# board2-c.net
KiCad netlist of a schematic drawn in EAGLE
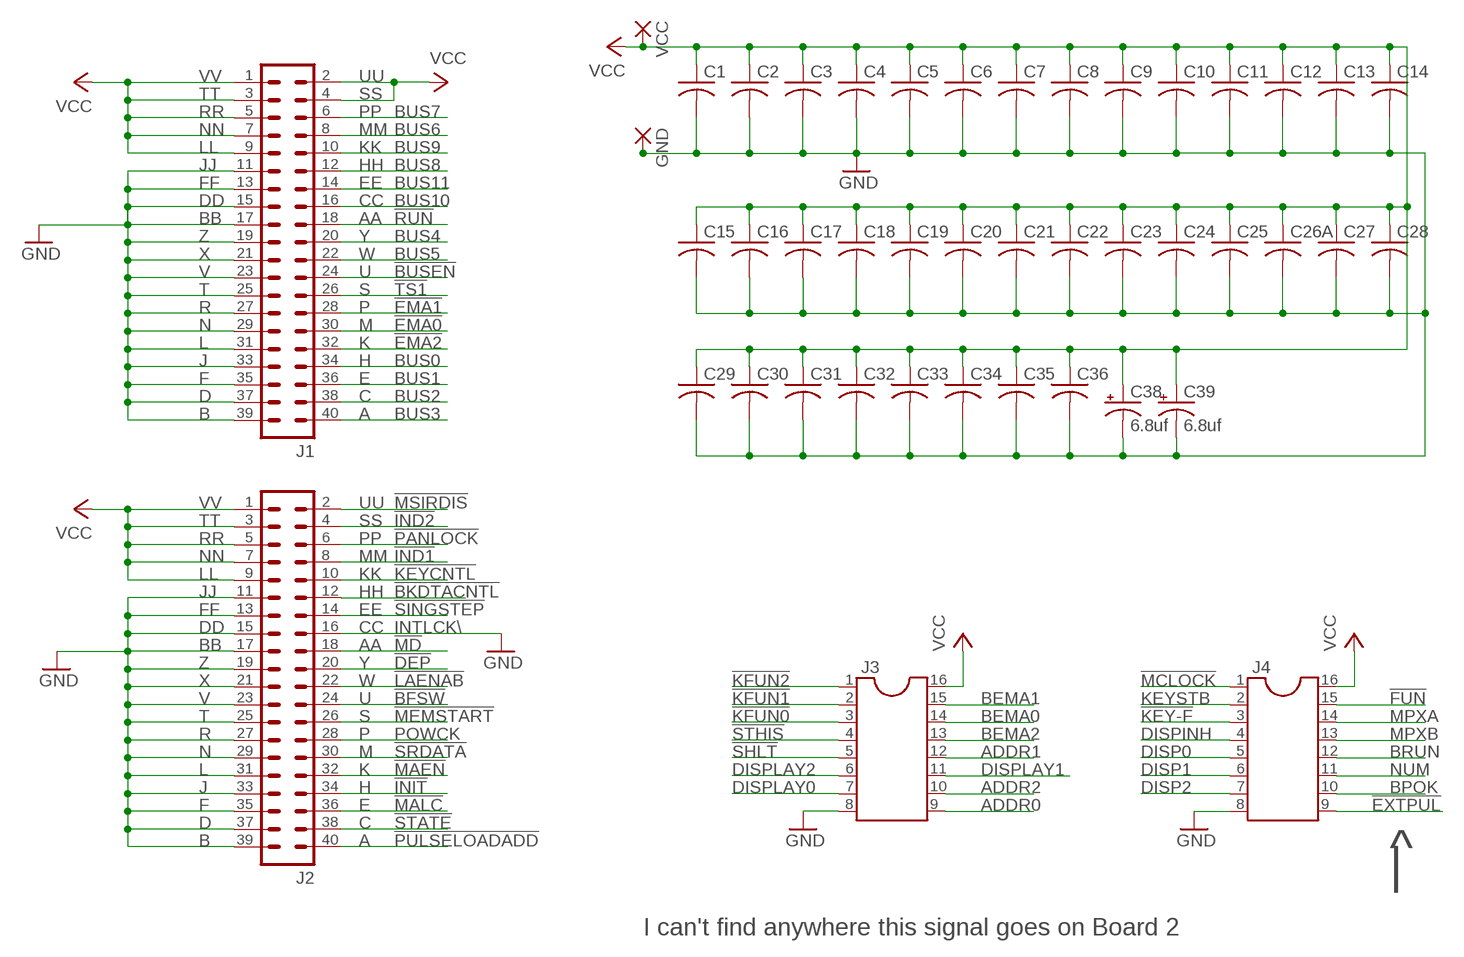
[diagram p0: schematic, sheet 1]
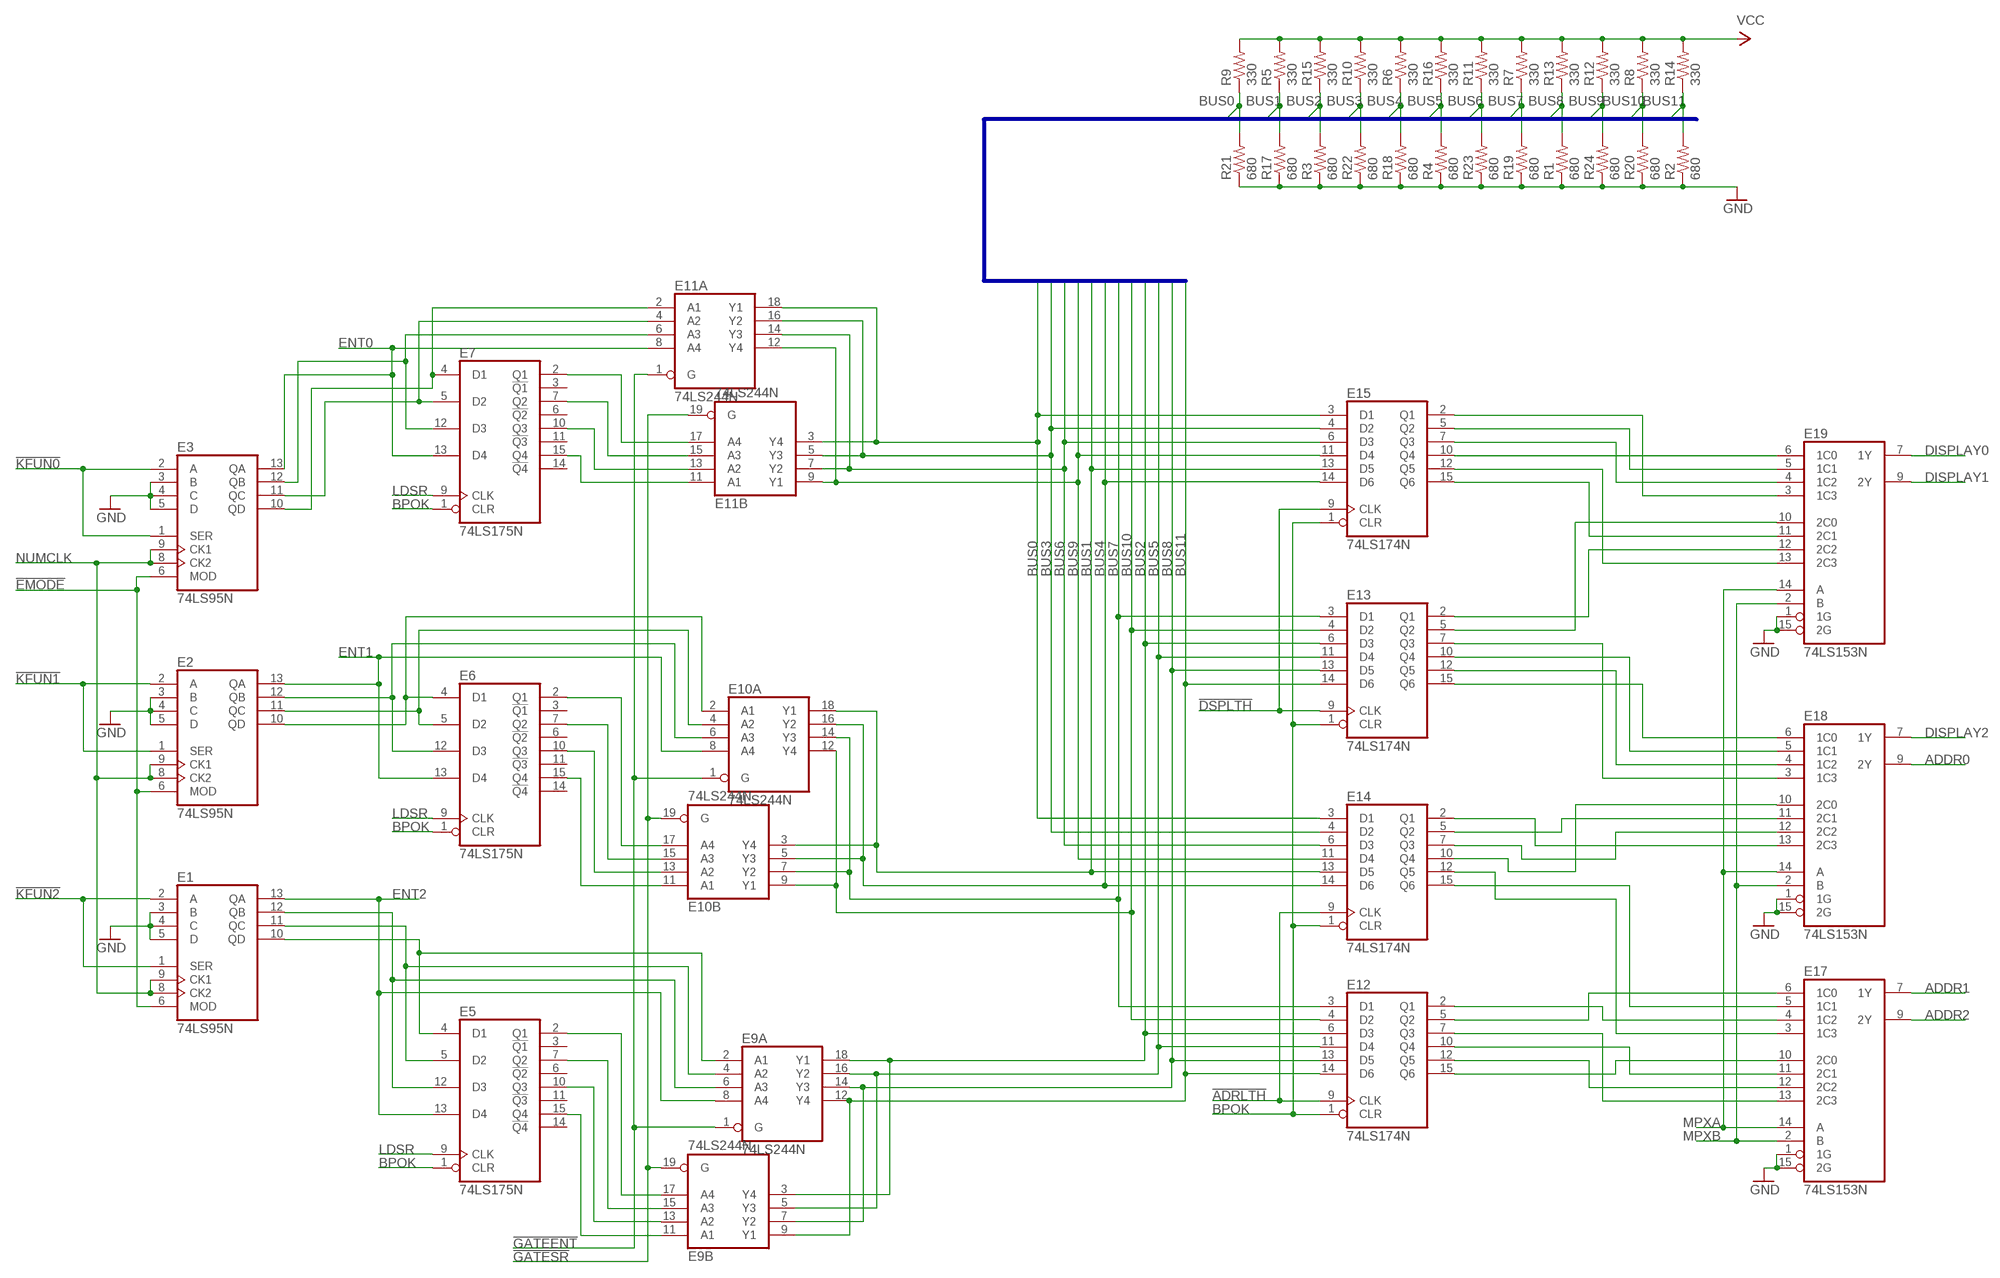
[diagram p1: schematic, sheet 2]
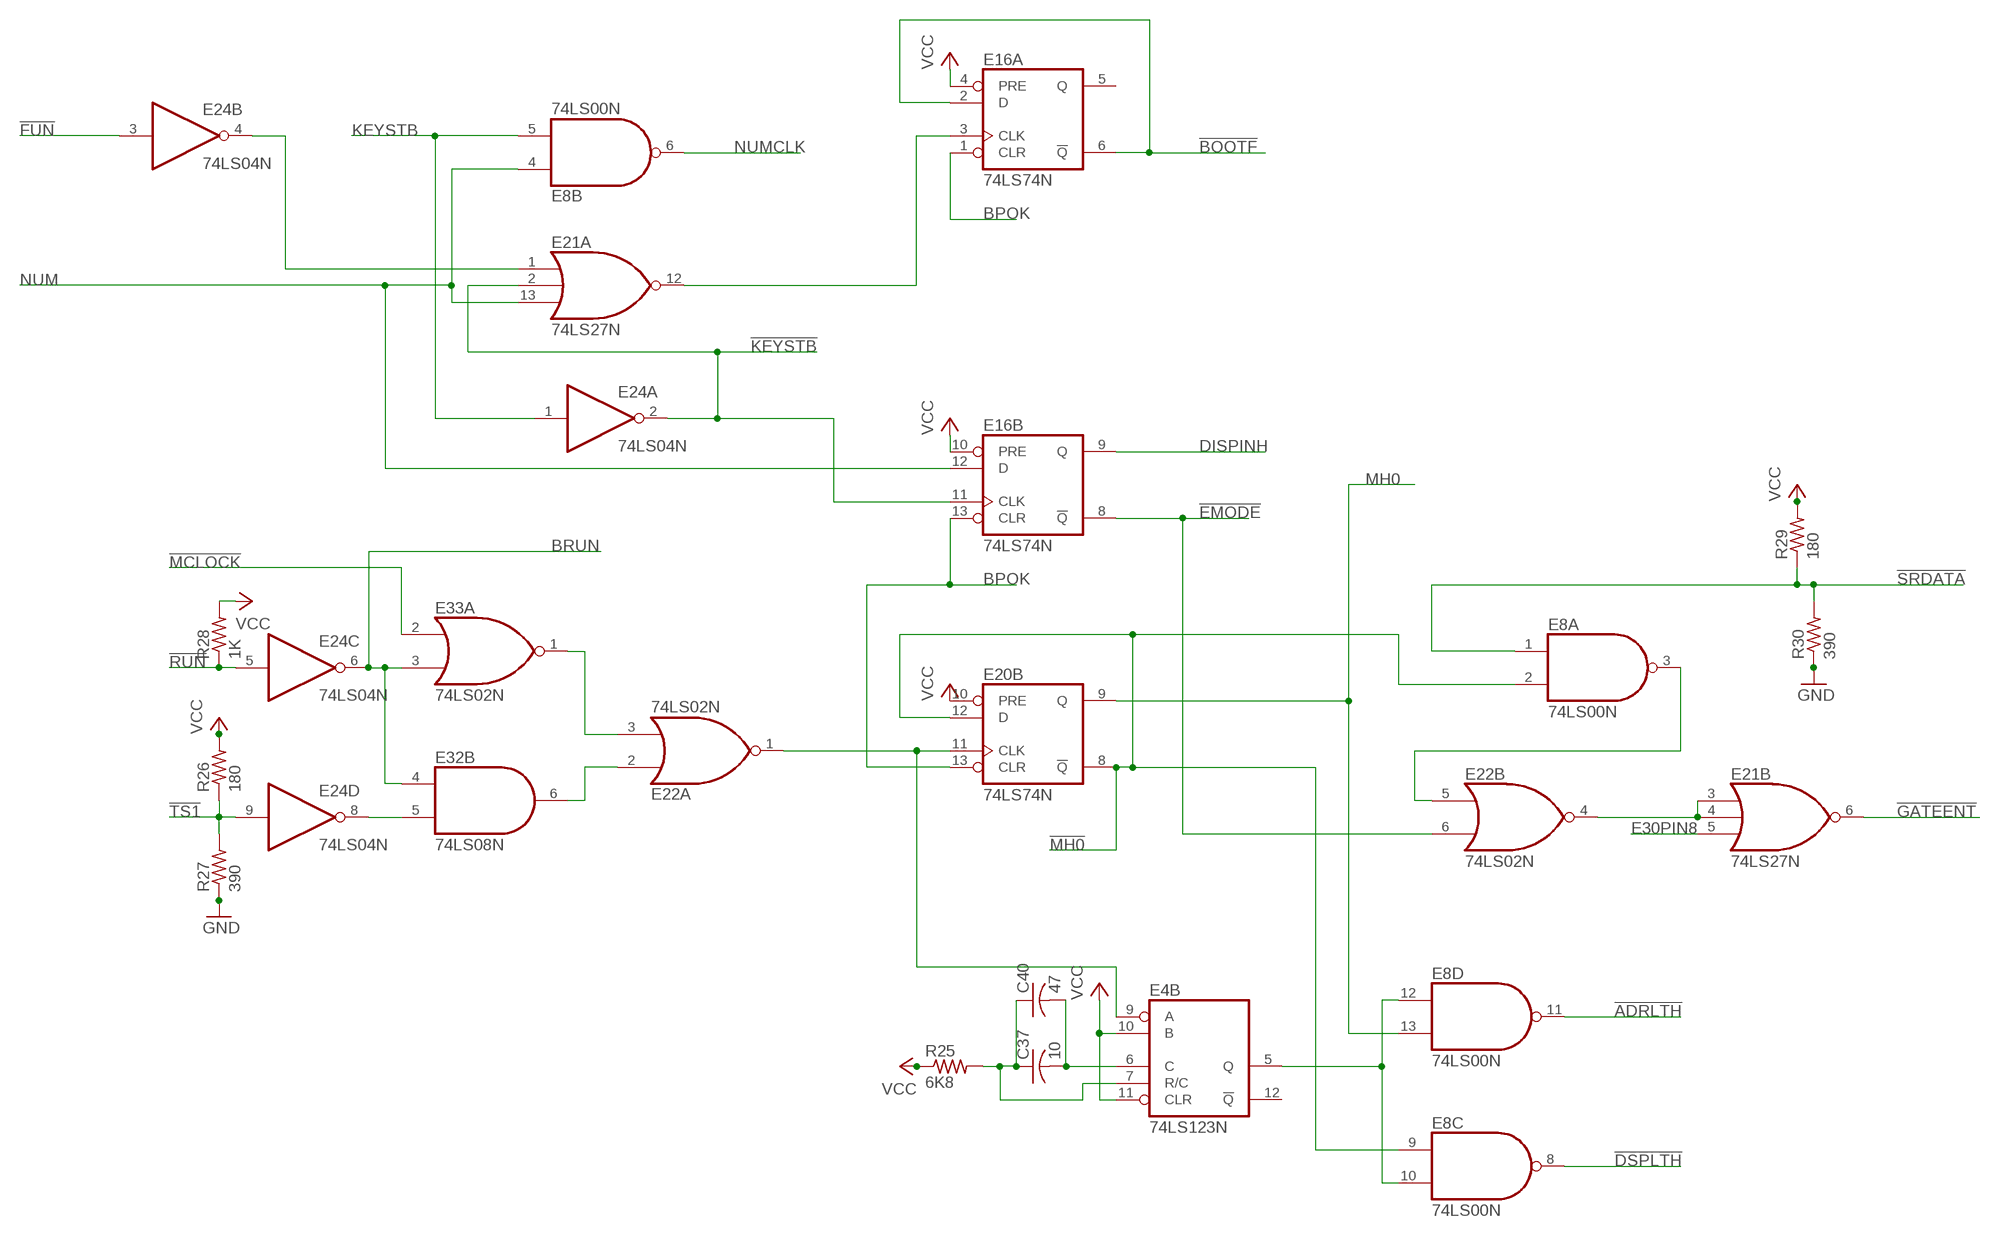
[diagram p2: schematic, sheet 3]
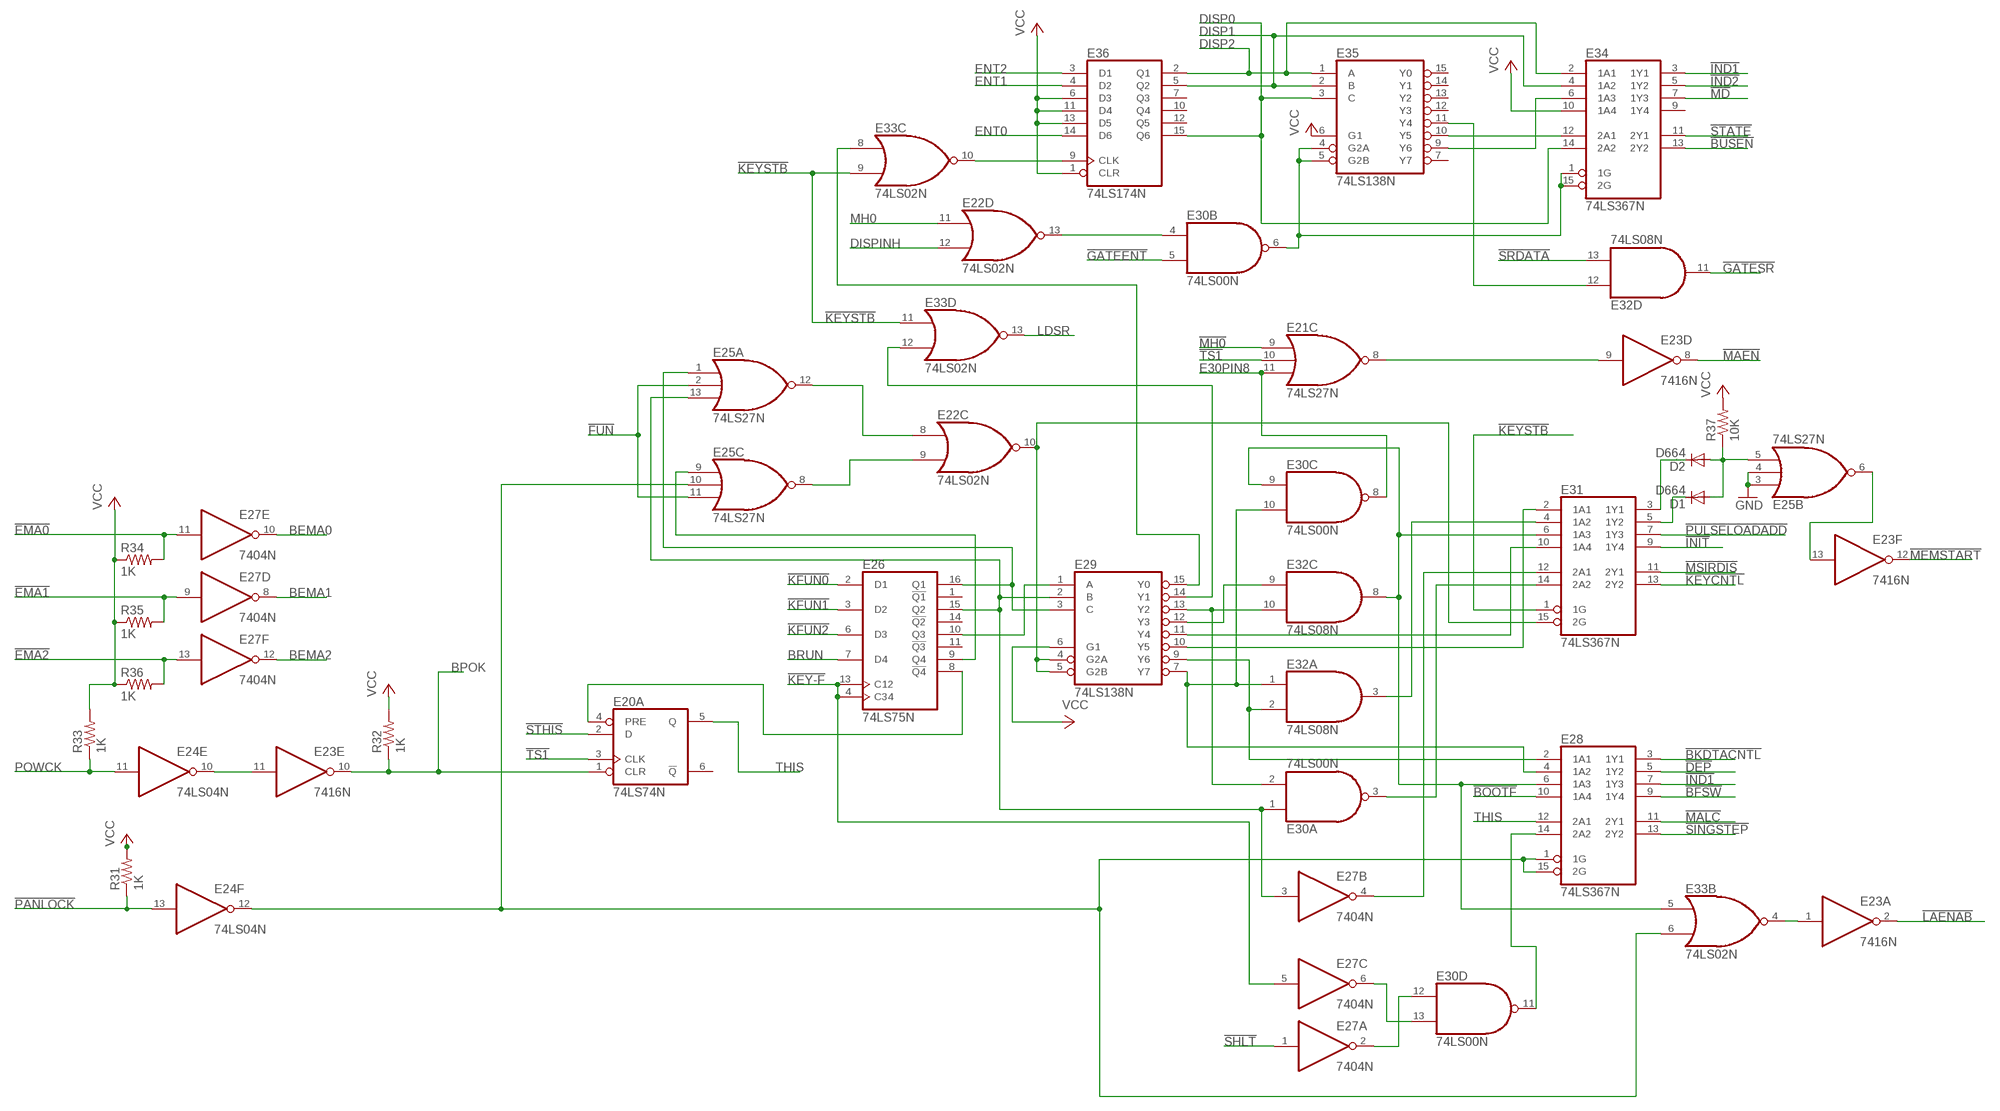
[diagram p3: schematic, sheet 4]

(export (version "E")
  (design (tool "Eeschema 10.0.6"))
  (components
    (comp (ref "C1")
      (value "C-US050-025X075")
      (footprint "eagle-import:C050-025X075")
      (libsource (lib "eagle-import") (part "C-US050-025X075"))
    )
    (comp (ref "C2")
      (value "C-US050-025X075")
      (footprint "eagle-import:C050-025X075")
      (libsource (lib "eagle-import") (part "C-US050-025X075"))
    )
    (comp (ref "C3")
      (value "C-US050-025X075")
      (footprint "eagle-import:C050-025X075")
      (libsource (lib "eagle-import") (part "C-US050-025X075"))
    )
    (comp (ref "C4")
      (value "C-US050-025X075")
      (footprint "eagle-import:C050-025X075")
      (libsource (lib "eagle-import") (part "C-US050-025X075"))
    )
    (comp (ref "C5")
      (value "C-US050-025X075")
      (footprint "eagle-import:C050-025X075")
      (libsource (lib "eagle-import") (part "C-US050-025X075"))
    )
    (comp (ref "C6")
      (value "C-US050-025X075")
      (footprint "eagle-import:C050-025X075")
      (libsource (lib "eagle-import") (part "C-US050-025X075"))
    )
    (comp (ref "C7")
      (value "C-US050-025X075")
      (footprint "eagle-import:C050-025X075")
      (libsource (lib "eagle-import") (part "C-US050-025X075"))
    )
    (comp (ref "C8")
      (value "C-US050-025X075")
      (footprint "eagle-import:C050-025X075")
      (libsource (lib "eagle-import") (part "C-US050-025X075"))
    )
    (comp (ref "C9")
      (value "C-US050-025X075")
      (footprint "eagle-import:C050-025X075")
      (libsource (lib "eagle-import") (part "C-US050-025X075"))
    )
    (comp (ref "C10")
      (value "C-US050-025X075")
      (footprint "eagle-import:C050-025X075")
      (libsource (lib "eagle-import") (part "C-US050-025X075"))
    )
    (comp (ref "C11")
      (value "C-US050-025X075")
      (footprint "eagle-import:C050-025X075")
      (libsource (lib "eagle-import") (part "C-US050-025X075"))
    )
    (comp (ref "C12")
      (value "C-US050-025X075")
      (footprint "eagle-import:C050-025X075")
      (libsource (lib "eagle-import") (part "C-US050-025X075"))
    )
    (comp (ref "C13")
      (value "C-US050-025X075")
      (footprint "eagle-import:C050-025X075")
      (libsource (lib "eagle-import") (part "C-US050-025X075"))
    )
    (comp (ref "C14")
      (value "C-US050-025X075")
      (footprint "eagle-import:C050-025X075")
      (libsource (lib "eagle-import") (part "C-US050-025X075"))
    )
    (comp (ref "C15")
      (value "C-US050-025X075")
      (footprint "eagle-import:C050-025X075")
      (libsource (lib "eagle-import") (part "C-US050-025X075"))
    )
    (comp (ref "C16")
      (value "C-US050-025X075")
      (footprint "eagle-import:C050-025X075")
      (libsource (lib "eagle-import") (part "C-US050-025X075"))
    )
    (comp (ref "C17")
      (value "C-US050-025X075")
      (footprint "eagle-import:C050-025X075")
      (libsource (lib "eagle-import") (part "C-US050-025X075"))
    )
    (comp (ref "C18")
      (value "C-US050-025X075")
      (footprint "eagle-import:C050-025X075")
      (libsource (lib "eagle-import") (part "C-US050-025X075"))
    )
    (comp (ref "C19")
      (value "C-US050-025X075")
      (footprint "eagle-import:C050-025X075")
      (libsource (lib "eagle-import") (part "C-US050-025X075"))
    )
    (comp (ref "C20")
      (value "C-US050-025X075")
      (footprint "eagle-import:C050-025X075")
      (libsource (lib "eagle-import") (part "C-US050-025X075"))
    )
    (comp (ref "C21")
      (value "C-US050-025X075")
      (footprint "eagle-import:C050-025X075")
      (libsource (lib "eagle-import") (part "C-US050-025X075"))
    )
    (comp (ref "C22")
      (value "C-US050-025X075")
      (footprint "eagle-import:C050-025X075")
      (libsource (lib "eagle-import") (part "C-US050-025X075"))
    )
    (comp (ref "C23")
      (value "C-US050-025X075")
      (footprint "eagle-import:C050-025X075")
      (libsource (lib "eagle-import") (part "C-US050-025X075"))
    )
    (comp (ref "C24")
      (value "C-US050-025X075")
      (footprint "eagle-import:C050-025X075")
      (libsource (lib "eagle-import") (part "C-US050-025X075"))
    )
    (comp (ref "C25")
      (value "C-US050-025X075")
      (footprint "eagle-import:C050-025X075")
      (libsource (lib "eagle-import") (part "C-US050-025X075"))
    )
    (comp (ref "C26A")
      (value "C-US050-025X075")
      (footprint "eagle-import:C050-025X075")
      (libsource (lib "eagle-import") (part "C-US050-025X075"))
    )
    (comp (ref "C27")
      (value "C-US050-025X075")
      (footprint "eagle-import:C050-025X075")
      (libsource (lib "eagle-import") (part "C-US050-025X075"))
    )
    (comp (ref "C28")
      (value "C-US050-025X075")
      (footprint "eagle-import:C050-025X075")
      (libsource (lib "eagle-import") (part "C-US050-025X075"))
    )
    (comp (ref "C29")
      (value "C-US050-025X075")
      (footprint "eagle-import:C050-025X075")
      (libsource (lib "eagle-import") (part "C-US050-025X075"))
    )
    (comp (ref "C30")
      (value "C-US050-025X075")
      (footprint "eagle-import:C050-025X075")
      (libsource (lib "eagle-import") (part "C-US050-025X075"))
    )
    (comp (ref "C31")
      (value "C-US050-025X075")
      (footprint "eagle-import:C050-025X075")
      (libsource (lib "eagle-import") (part "C-US050-025X075"))
    )
    (comp (ref "C32")
      (value "C-US050-025X075")
      (footprint "eagle-import:C050-025X075")
      (libsource (lib "eagle-import") (part "C-US050-025X075"))
    )
    (comp (ref "C33")
      (value "C-US050-025X075")
      (footprint "eagle-import:C050-025X075")
      (libsource (lib "eagle-import") (part "C-US050-025X075"))
    )
    (comp (ref "C34")
      (value "C-US050-025X075")
      (footprint "eagle-import:C050-025X075")
      (libsource (lib "eagle-import") (part "C-US050-025X075"))
    )
    (comp (ref "C35")
      (value "C-US050-025X075")
      (footprint "eagle-import:C050-025X075")
      (libsource (lib "eagle-import") (part "C-US050-025X075"))
    )
    (comp (ref "C36")
      (value "C-US050-025X075")
      (footprint "eagle-import:C050-025X075")
      (libsource (lib "eagle-import") (part "C-US050-025X075"))
    )
    (comp (ref "C38")
      (value "6.8uf")
      (footprint "eagle-import:E15-5")
      (libsource (lib "eagle-import") (part "CPOL-USE15-5AXIAL"))
    )
    (comp (ref "C39")
      (value "6.8uf")
      (footprint "eagle-import:E15-5")
      (libsource (lib "eagle-import") (part "CPOL-USE15-5AXIAL"))
    )
    (comp (ref "GND")
      (value "3,81/1,4")
      (footprint "eagle-import:3,81_1,4")
      (libsource (lib "eagle-import") (part "3,81/1,4"))
    )
    (comp (ref "J1")
      (value "40H")
      (footprint "eagle-import:40H")
      (libsource (lib "eagle-import") (part "40H"))
    )
    (comp (ref "J2")
      (value "40H")
      (footprint "eagle-import:40H")
      (libsource (lib "eagle-import") (part "40H"))
    )
    (comp (ref "J3")
      (value "DIL16S")
      (footprint "eagle-import:SOCKET-16")
      (libsource (lib "eagle-import") (part "DIL16S"))
    )
    (comp (ref "J4")
      (value "DIL16S")
      (footprint "eagle-import:SOCKET-16")
      (libsource (lib "eagle-import") (part "DIL16S"))
    )
    (comp (ref "VCC")
      (value "3,81/1,4")
      (footprint "eagle-import:3,81_1,4")
      (libsource (lib "eagle-import") (part "3,81/1,4"))
    )
    (comp (ref "D1")
      (value "D664")
      (footprint "eagle-import:DO35-10")
      (libsource (lib "eagle-import") (part "1N4148DO35-10"))
    )
    (comp (ref "D2")
      (value "D664")
      (footprint "eagle-import:DO35-10")
      (libsource (lib "eagle-import") (part "1N4148DO35-10"))
    )
    (comp (ref "E20")
      (value "74LS74N")
      (footprint "eagle-import:DIL14")
      (libsource (lib "eagle-import") (part "7474NLS"))
    )
    (comp (ref "E21")
      (value "74LS27N")
      (footprint "eagle-import:DIL14")
      (libsource (lib "eagle-import") (part "7427NLS"))
    )
    (comp (ref "E22")
      (value "74LS02N")
      (footprint "eagle-import:DIL14")
      (libsource (lib "eagle-import") (part "7402NLS"))
    )
    (comp (ref "E23")
      (value "7416N")
      (footprint "eagle-import:DIL14")
      (libsource (lib "eagle-import") (part "7416N"))
    )
    (comp (ref "E24")
      (value "74LS04N")
      (footprint "eagle-import:DIL14")
      (libsource (lib "eagle-import") (part "7404NLS"))
    )
    (comp (ref "E25")
      (value "74LS27N")
      (footprint "eagle-import:DIL14")
      (libsource (lib "eagle-import") (part "7427NLS"))
    )
    (comp (ref "E26")
      (value "74LS75N")
      (footprint "eagle-import:DIL16")
      (libsource (lib "eagle-import") (part "7475NLS"))
    )
    (comp (ref "E27")
      (value "7404N")
      (footprint "eagle-import:DIL14")
      (libsource (lib "eagle-import") (part "7404N"))
    )
    (comp (ref "E28")
      (value "74LS367N")
      (footprint "eagle-import:DIL16")
      (libsource (lib "eagle-import") (part "74367N"))
    )
    (comp (ref "E29")
      (value "74LS138N")
      (footprint "eagle-import:DIL16")
      (libsource (lib "eagle-import") (part "74138NLS"))
    )
    (comp (ref "E30")
      (value "74LS00N")
      (footprint "eagle-import:DIL14")
      (libsource (lib "eagle-import") (part "7400NLS"))
    )
    (comp (ref "E31")
      (value "74LS367N")
      (footprint "eagle-import:DIL16")
      (libsource (lib "eagle-import") (part "74367N"))
    )
    (comp (ref "E32")
      (value "74LS08N")
      (footprint "eagle-import:DIL14")
      (libsource (lib "eagle-import") (part "7408NLS"))
    )
    (comp (ref "E33")
      (value "74LS02N")
      (footprint "eagle-import:DIL14")
      (libsource (lib "eagle-import") (part "7402NLS"))
    )
    (comp (ref "E34")
      (value "74LS367N")
      (footprint "eagle-import:DIL16")
      (libsource (lib "eagle-import") (part "74367N"))
    )
    (comp (ref "E35")
      (value "74LS138N")
      (footprint "eagle-import:DIL16")
      (libsource (lib "eagle-import") (part "74138NLS"))
    )
    (comp (ref "E36")
      (value "74LS174N")
      (footprint "eagle-import:DIL16")
      (libsource (lib "eagle-import") (part "74174NLS"))
    )
    (comp (ref "R31")
      (value "1K")
      (footprint "eagle-import:0207_10")
      (libsource (lib "eagle-import") (part "R-US_0207/10"))
    )
    (comp (ref "R32")
      (value "1K")
      (footprint "eagle-import:0207_10")
      (libsource (lib "eagle-import") (part "R-US_0207/10"))
    )
    (comp (ref "R33")
      (value "1K")
      (footprint "eagle-import:0207_10")
      (libsource (lib "eagle-import") (part "R-US_0207/10"))
    )
    (comp (ref "R34")
      (value "1K")
      (footprint "eagle-import:0207_10")
      (libsource (lib "eagle-import") (part "R-US_0207/10"))
    )
    (comp (ref "R35")
      (value "1K")
      (footprint "eagle-import:0207_10")
      (libsource (lib "eagle-import") (part "R-US_0207/10"))
    )
    (comp (ref "R36")
      (value "1K")
      (footprint "eagle-import:0207_10")
      (libsource (lib "eagle-import") (part "R-US_0207/10"))
    )
    (comp (ref "R37")
      (value "10K")
      (footprint "eagle-import:0207_10")
      (libsource (lib "eagle-import") (part "R-US_0207/10"))
    )
    (comp (ref "C37")
      (value "10")
      (footprint "eagle-import:C050-025X075")
      (libsource (lib "eagle-import") (part "C-US050-025X075"))
    )
    (comp (ref "C40")
      (value "47")
      (footprint "eagle-import:C050-025X075")
      (libsource (lib "eagle-import") (part "C-US050-025X075"))
    )
    (comp (ref "E4")
      (value "74LS123N")
      (footprint "eagle-import:DIL16")
      (libsource (lib "eagle-import") (part "74123NLS"))
    )
    (comp (ref "E8")
      (value "74LS00N")
      (footprint "eagle-import:DIL14")
      (libsource (lib "eagle-import") (part "7400NLS"))
    )
    (comp (ref "E16")
      (value "74LS74N")
      (footprint "eagle-import:DIL14")
      (libsource (lib "eagle-import") (part "7474NLS"))
    )
    (comp (ref "R25")
      (value "6K8")
      (footprint "eagle-import:0207_10")
      (libsource (lib "eagle-import") (part "R-US_0207/10"))
    )
    (comp (ref "R26")
      (value "180")
      (footprint "eagle-import:0207_10")
      (libsource (lib "eagle-import") (part "R-US_0207/10"))
    )
    (comp (ref "R27")
      (value "390")
      (footprint "eagle-import:0207_10")
      (libsource (lib "eagle-import") (part "R-US_0207/10"))
    )
    (comp (ref "R28")
      (value "1K")
      (footprint "eagle-import:0207_10")
      (libsource (lib "eagle-import") (part "R-US_0207/10"))
    )
    (comp (ref "R29")
      (value "180")
      (footprint "eagle-import:0207_10")
      (libsource (lib "eagle-import") (part "R-US_0207/10"))
    )
    (comp (ref "R30")
      (value "390")
      (footprint "eagle-import:0207_10")
      (libsource (lib "eagle-import") (part "R-US_0207/10"))
    )
    (comp (ref "E1")
      (value "74LS95N")
      (footprint "eagle-import:DIL14")
      (libsource (lib "eagle-import") (part "7495NLS"))
    )
    (comp (ref "E2")
      (value "74LS95N")
      (footprint "eagle-import:DIL14")
      (libsource (lib "eagle-import") (part "7495NLS"))
    )
    (comp (ref "E3")
      (value "74LS95N")
      (footprint "eagle-import:DIL14")
      (libsource (lib "eagle-import") (part "7495NLS"))
    )
    (comp (ref "E5")
      (value "74LS175N")
      (footprint "eagle-import:DIL16")
      (libsource (lib "eagle-import") (part "74175NLS"))
    )
    (comp (ref "E6")
      (value "74LS175N")
      (footprint "eagle-import:DIL16")
      (libsource (lib "eagle-import") (part "74175NLS"))
    )
    (comp (ref "E7")
      (value "74LS175N")
      (footprint "eagle-import:DIL16")
      (libsource (lib "eagle-import") (part "74175NLS"))
    )
    (comp (ref "E9")
      (value "74LS244N")
      (footprint "eagle-import:DIL20")
      (libsource (lib "eagle-import") (part "74244NS"))
    )
    (comp (ref "E10")
      (value "74LS244N")
      (footprint "eagle-import:DIL20")
      (libsource (lib "eagle-import") (part "74244NS"))
    )
    (comp (ref "E11")
      (value "74LS244N")
      (footprint "eagle-import:DIL20")
      (libsource (lib "eagle-import") (part "74244NS"))
    )
    (comp (ref "E12")
      (value "74LS174N")
      (footprint "eagle-import:DIL16")
      (libsource (lib "eagle-import") (part "74174NLS"))
    )
    (comp (ref "E13")
      (value "74LS174N")
      (footprint "eagle-import:DIL16")
      (libsource (lib "eagle-import") (part "74174NLS"))
    )
    (comp (ref "E14")
      (value "74LS174N")
      (footprint "eagle-import:DIL16")
      (libsource (lib "eagle-import") (part "74174NLS"))
    )
    (comp (ref "E15")
      (value "74LS174N")
      (footprint "eagle-import:DIL16")
      (libsource (lib "eagle-import") (part "74174NLS"))
    )
    (comp (ref "E17")
      (value "74LS153N")
      (footprint "eagle-import:DIL16")
      (libsource (lib "eagle-import") (part "74153NLS"))
    )
    (comp (ref "E18")
      (value "74LS153N")
      (footprint "eagle-import:DIL16")
      (libsource (lib "eagle-import") (part "74153NLS"))
    )
    (comp (ref "E19")
      (value "74LS153N")
      (footprint "eagle-import:DIL16")
      (libsource (lib "eagle-import") (part "74153NLS"))
    )
    (comp (ref "R1")
      (value "680")
      (footprint "eagle-import:0207_10")
      (libsource (lib "eagle-import") (part "R-US_0207/10"))
    )
    (comp (ref "R2")
      (value "680")
      (footprint "eagle-import:0207_10")
      (libsource (lib "eagle-import") (part "R-US_0207/10"))
    )
    (comp (ref "R3")
      (value "680")
      (footprint "eagle-import:0207_10")
      (libsource (lib "eagle-import") (part "R-US_0207/10"))
    )
    (comp (ref "R4")
      (value "680")
      (footprint "eagle-import:0207_10")
      (libsource (lib "eagle-import") (part "R-US_0207/10"))
    )
    (comp (ref "R5")
      (value "330")
      (footprint "eagle-import:0207_10")
      (libsource (lib "eagle-import") (part "R-US_0207/10"))
    )
    (comp (ref "R6")
      (value "330")
      (footprint "eagle-import:0207_10")
      (libsource (lib "eagle-import") (part "R-US_0207/10"))
    )
    (comp (ref "R7")
      (value "330")
      (footprint "eagle-import:0207_10")
      (libsource (lib "eagle-import") (part "R-US_0207/10"))
    )
    (comp (ref "R8")
      (value "330")
      (footprint "eagle-import:0207_10")
      (libsource (lib "eagle-import") (part "R-US_0207/10"))
    )
    (comp (ref "R9")
      (value "330")
      (footprint "eagle-import:0207_10")
      (libsource (lib "eagle-import") (part "R-US_0207/10"))
    )
    (comp (ref "R10")
      (value "330")
      (footprint "eagle-import:0207_10")
      (libsource (lib "eagle-import") (part "R-US_0207/10"))
    )
    (comp (ref "R11")
      (value "330")
      (footprint "eagle-import:0207_10")
      (libsource (lib "eagle-import") (part "R-US_0207/10"))
    )
    (comp (ref "R12")
      (value "330")
      (footprint "eagle-import:0207_10")
      (libsource (lib "eagle-import") (part "R-US_0207/10"))
    )
    (comp (ref "R13")
      (value "330")
      (footprint "eagle-import:0207_10")
      (libsource (lib "eagle-import") (part "R-US_0207/10"))
    )
    (comp (ref "R14")
      (value "330")
      (footprint "eagle-import:0207_10")
      (libsource (lib "eagle-import") (part "R-US_0207/10"))
    )
    (comp (ref "R15")
      (value "330")
      (footprint "eagle-import:0207_10")
      (libsource (lib "eagle-import") (part "R-US_0207/10"))
    )
    (comp (ref "R16")
      (value "330")
      (footprint "eagle-import:0207_10")
      (libsource (lib "eagle-import") (part "R-US_0207/10"))
    )
    (comp (ref "R17")
      (value "680")
      (footprint "eagle-import:0207_10")
      (libsource (lib "eagle-import") (part "R-US_0207/10"))
    )
    (comp (ref "R18")
      (value "680")
      (footprint "eagle-import:0207_10")
      (libsource (lib "eagle-import") (part "R-US_0207/10"))
    )
    (comp (ref "R19")
      (value "680")
      (footprint "eagle-import:0207_10")
      (libsource (lib "eagle-import") (part "R-US_0207/10"))
    )
    (comp (ref "R20")
      (value "680")
      (footprint "eagle-import:0207_10")
      (libsource (lib "eagle-import") (part "R-US_0207/10"))
    )
    (comp (ref "R21")
      (value "680")
      (footprint "eagle-import:0207_10")
      (libsource (lib "eagle-import") (part "R-US_0207/10"))
    )
    (comp (ref "R22")
      (value "680")
      (footprint "eagle-import:0207_10")
      (libsource (lib "eagle-import") (part "R-US_0207/10"))
    )
    (comp (ref "R23")
      (value "680")
      (footprint "eagle-import:0207_10")
      (libsource (lib "eagle-import") (part "R-US_0207/10"))
    )
    (comp (ref "R24")
      (value "680")
      (footprint "eagle-import:0207_10")
      (libsource (lib "eagle-import") (part "R-US_0207/10"))
    )
  )
  (nets
    (net (code "1") (name "ADDR0") (class "Default")
      (node (ref "E18") (pin "9") (pinfunction "2Y_9") (pintype "output"))
      (node (ref "J3") (pin "9") (pinfunction "9_9") (pintype "passive"))
    )
    (net (code "2") (name "ADDR1") (class "Default")
      (node (ref "E17") (pin "7") (pinfunction "1Y_7") (pintype "output"))
      (node (ref "J3") (pin "12") (pinfunction "12_12") (pintype "passive"))
    )
    (net (code "3") (name "ADDR2") (class "Default")
      (node (ref "E17") (pin "9") (pinfunction "2Y_9") (pintype "output"))
      (node (ref "J3") (pin "10") (pinfunction "10_10") (pintype "passive"))
    )
    (net (code "4") (name "BEMA0") (class "Default")
      (node (ref "E27") (pin "10") (pinfunction "O_10") (pintype "output"))
      (node (ref "J3") (pin "14") (pinfunction "14_14") (pintype "passive"))
    )
    (net (code "5") (name "BEMA1") (class "Default")
      (node (ref "E27") (pin "8") (pinfunction "O_8") (pintype "output"))
      (node (ref "J3") (pin "15") (pinfunction "15_15") (pintype "passive"))
    )
    (net (code "6") (name "BEMA2") (class "Default")
      (node (ref "E27") (pin "12") (pinfunction "O_12") (pintype "output"))
      (node (ref "J3") (pin "13") (pinfunction "13_13") (pintype "passive"))
    )
    (net (code "7") (name "BPOK") (class "Default")
      (node (ref "E12") (pin "1") (pinfunction "CLR_1") (pintype "input"))
      (node (ref "E13") (pin "1") (pinfunction "CLR_1") (pintype "input"))
      (node (ref "E14") (pin "1") (pinfunction "CLR_1") (pintype "input"))
      (node (ref "E15") (pin "1") (pinfunction "CLR_1") (pintype "input"))
      (node (ref "E16") (pin "1") (pinfunction "CLR_1") (pintype "input"))
      (node (ref "E16") (pin "13") (pinfunction "CLR_13") (pintype "input"))
      (node (ref "E20") (pin "1") (pinfunction "CLR_1") (pintype "input"))
      (node (ref "E20") (pin "13") (pinfunction "CLR_13") (pintype "input"))
      (node (ref "E23") (pin "10") (pinfunction "O_10") (pintype "open_collector"))
      (node (ref "E5") (pin "1") (pinfunction "CLR_1") (pintype "input"))
      (node (ref "E6") (pin "1") (pinfunction "CLR_1") (pintype "input"))
      (node (ref "E7") (pin "1") (pinfunction "CLR_1") (pintype "input"))
      (node (ref "J4") (pin "10") (pinfunction "10_10") (pintype "passive"))
      (node (ref "R32") (pin "1") (pinfunction "1_1") (pintype "passive"))
    )
    (net (code "8") (name "BRUN") (class "Default")
      (node (ref "E24") (pin "6") (pinfunction "O_6") (pintype "output"))
      (node (ref "E26") (pin "7") (pinfunction "D4_7") (pintype "input"))
      (node (ref "E32") (pin "4") (pinfunction "I0_4") (pintype "input"))
      (node (ref "E33") (pin "3") (pinfunction "I1_3") (pintype "input"))
      (node (ref "J4") (pin "12") (pinfunction "12_12") (pintype "passive"))
    )
    (net (code "9") (name "BUS0") (class "Default")
      (node (ref "E11") (pin "18") (pinfunction "Y1_18") (pintype "tri_state"))
      (node (ref "E11") (pin "3") (pinfunction "Y4_3") (pintype "tri_state"))
      (node (ref "E14") (pin "3") (pinfunction "D1_3") (pintype "input"))
      (node (ref "E15") (pin "3") (pinfunction "D1_3") (pintype "input"))
      (node (ref "J1") (pin "34") (pinfunction "34_34") (pintype "passive"))
      (node (ref "R21") (pin "2") (pinfunction "2_2") (pintype "passive"))
      (node (ref "R9") (pin "1") (pinfunction "1_1") (pintype "passive"))
    )
    (net (code "10") (name "BUS1") (class "Default")
      (node (ref "E10") (pin "18") (pinfunction "Y1_18") (pintype "tri_state"))
      (node (ref "E10") (pin "3") (pinfunction "Y4_3") (pintype "tri_state"))
      (node (ref "E14") (pin "13") (pinfunction "D5_13") (pintype "input"))
      (node (ref "E15") (pin "13") (pinfunction "D5_13") (pintype "input"))
      (node (ref "J1") (pin "36") (pinfunction "36_36") (pintype "passive"))
      (node (ref "R17") (pin "2") (pinfunction "2_2") (pintype "passive"))
      (node (ref "R5") (pin "1") (pinfunction "1_1") (pintype "passive"))
    )
    (net (code "11") (name "BUS2") (class "Default")
      (node (ref "E12") (pin "6") (pinfunction "D3_6") (pintype "input"))
      (node (ref "E13") (pin "6") (pinfunction "D3_6") (pintype "input"))
      (node (ref "E9") (pin "18") (pinfunction "Y1_18") (pintype "tri_state"))
      (node (ref "E9") (pin "3") (pinfunction "Y4_3") (pintype "tri_state"))
      (node (ref "J1") (pin "38") (pinfunction "38_38") (pintype "passive"))
      (node (ref "R15") (pin "1") (pinfunction "1_1") (pintype "passive"))
      (node (ref "R3") (pin "2") (pinfunction "2_2") (pintype "passive"))
    )
    (net (code "12") (name "BUS3") (class "Default")
      (node (ref "E11") (pin "16") (pinfunction "Y2_16") (pintype "tri_state"))
      (node (ref "E11") (pin "5") (pinfunction "Y3_5") (pintype "tri_state"))
      (node (ref "E14") (pin "4") (pinfunction "D2_4") (pintype "input"))
      (node (ref "E15") (pin "4") (pinfunction "D2_4") (pintype "input"))
      (node (ref "J1") (pin "40") (pinfunction "40_40") (pintype "passive"))
      (node (ref "R10") (pin "1") (pinfunction "1_1") (pintype "passive"))
      (node (ref "R22") (pin "2") (pinfunction "2_2") (pintype "passive"))
    )
    (net (code "13") (name "BUS4") (class "Default")
      (node (ref "E10") (pin "16") (pinfunction "Y2_16") (pintype "tri_state"))
      (node (ref "E10") (pin "5") (pinfunction "Y3_5") (pintype "tri_state"))
      (node (ref "E14") (pin "14") (pinfunction "D6_14") (pintype "input"))
      (node (ref "E15") (pin "14") (pinfunction "D6_14") (pintype "input"))
      (node (ref "J1") (pin "20") (pinfunction "20_20") (pintype "passive"))
      (node (ref "R18") (pin "2") (pinfunction "2_2") (pintype "passive"))
      (node (ref "R6") (pin "1") (pinfunction "1_1") (pintype "passive"))
    )
    (net (code "14") (name "BUS5") (class "Default")
      (node (ref "E12") (pin "11") (pinfunction "D4_11") (pintype "input"))
      (node (ref "E13") (pin "11") (pinfunction "D4_11") (pintype "input"))
      (node (ref "E9") (pin "16") (pinfunction "Y2_16") (pintype "tri_state"))
      (node (ref "E9") (pin "5") (pinfunction "Y3_5") (pintype "tri_state"))
      (node (ref "J1") (pin "22") (pinfunction "22_22") (pintype "passive"))
      (node (ref "R16") (pin "1") (pinfunction "1_1") (pintype "passive"))
      (node (ref "R4") (pin "2") (pinfunction "2_2") (pintype "passive"))
    )
    (net (code "15") (name "BUS6") (class "Default")
      (node (ref "E11") (pin "14") (pinfunction "Y3_14") (pintype "tri_state"))
      (node (ref "E11") (pin "7") (pinfunction "Y2_7") (pintype "tri_state"))
      (node (ref "E14") (pin "6") (pinfunction "D3_6") (pintype "input"))
      (node (ref "E15") (pin "6") (pinfunction "D3_6") (pintype "input"))
      (node (ref "J1") (pin "8") (pinfunction "8_8") (pintype "passive"))
      (node (ref "R11") (pin "1") (pinfunction "1_1") (pintype "passive"))
      (node (ref "R23") (pin "2") (pinfunction "2_2") (pintype "passive"))
    )
    (net (code "16") (name "BUS7") (class "Default")
      (node (ref "E10") (pin "14") (pinfunction "Y3_14") (pintype "tri_state"))
      (node (ref "E10") (pin "7") (pinfunction "Y2_7") (pintype "tri_state"))
      (node (ref "E12") (pin "3") (pinfunction "D1_3") (pintype "input"))
      (node (ref "E13") (pin "3") (pinfunction "D1_3") (pintype "input"))
      (node (ref "J1") (pin "6") (pinfunction "6_6") (pintype "passive"))
      (node (ref "R19") (pin "2") (pinfunction "2_2") (pintype "passive"))
      (node (ref "R7") (pin "1") (pinfunction "1_1") (pintype "passive"))
    )
    (net (code "17") (name "BUS8") (class "Default")
      (node (ref "E12") (pin "13") (pinfunction "D5_13") (pintype "input"))
      (node (ref "E13") (pin "13") (pinfunction "D5_13") (pintype "input"))
      (node (ref "E9") (pin "14") (pinfunction "Y3_14") (pintype "tri_state"))
      (node (ref "E9") (pin "7") (pinfunction "Y2_7") (pintype "tri_state"))
      (node (ref "J1") (pin "12") (pinfunction "12_12") (pintype "passive"))
      (node (ref "R1") (pin "2") (pinfunction "2_2") (pintype "passive"))
      (node (ref "R13") (pin "1") (pinfunction "1_1") (pintype "passive"))
    )
    (net (code "18") (name "BUS9") (class "Default")
      (node (ref "E11") (pin "12") (pinfunction "Y4_12") (pintype "tri_state"))
      (node (ref "E11") (pin "9") (pinfunction "Y1_9") (pintype "tri_state"))
      (node (ref "E14") (pin "11") (pinfunction "D4_11") (pintype "input"))
      (node (ref "E15") (pin "11") (pinfunction "D4_11") (pintype "input"))
      (node (ref "J1") (pin "10") (pinfunction "10_10") (pintype "passive"))
      (node (ref "R12") (pin "1") (pinfunction "1_1") (pintype "passive"))
      (node (ref "R24") (pin "2") (pinfunction "2_2") (pintype "passive"))
    )
    (net (code "19") (name "BUS10") (class "Default")
      (node (ref "E10") (pin "12") (pinfunction "Y4_12") (pintype "tri_state"))
      (node (ref "E10") (pin "9") (pinfunction "Y1_9") (pintype "tri_state"))
      (node (ref "E12") (pin "4") (pinfunction "D2_4") (pintype "input"))
      (node (ref "E13") (pin "4") (pinfunction "D2_4") (pintype "input"))
      (node (ref "J1") (pin "16") (pinfunction "16_16") (pintype "passive"))
      (node (ref "R20") (pin "2") (pinfunction "2_2") (pintype "passive"))
      (node (ref "R8") (pin "1") (pinfunction "1_1") (pintype "passive"))
    )
    (net (code "20") (name "BUS11") (class "Default")
      (node (ref "E12") (pin "14") (pinfunction "D6_14") (pintype "input"))
      (node (ref "E13") (pin "14") (pinfunction "D6_14") (pintype "input"))
      (node (ref "E9") (pin "12") (pinfunction "Y4_12") (pintype "tri_state"))
      (node (ref "E9") (pin "9") (pinfunction "Y1_9") (pintype "tri_state"))
      (node (ref "J1") (pin "14") (pinfunction "14_14") (pintype "passive"))
      (node (ref "R14") (pin "1") (pinfunction "1_1") (pintype "passive"))
      (node (ref "R2") (pin "2") (pinfunction "2_2") (pintype "passive"))
    )
    (net (code "21") (name "DISP0") (class "Default")
      (node (ref "E34") (pin "14") (pinfunction "2A2_14") (pintype "input"))
      (node (ref "E35") (pin "3") (pinfunction "C_3") (pintype "input"))
      (node (ref "E36") (pin "15") (pinfunction "Q6_15") (pintype "output"))
      (node (ref "J4") (pin "5") (pinfunction "5_5") (pintype "passive"))
    )
    (net (code "22") (name "DISP1") (class "Default")
      (node (ref "E34") (pin "4") (pinfunction "1A2_4") (pintype "input"))
      (node (ref "E35") (pin "2") (pinfunction "B_2") (pintype "input"))
      (node (ref "E36") (pin "5") (pinfunction "Q2_5") (pintype "output"))
      (node (ref "J4") (pin "6") (pinfunction "6_6") (pintype "passive"))
    )
    (net (code "23") (name "DISP2") (class "Default")
      (node (ref "E34") (pin "2") (pinfunction "1A1_2") (pintype "input"))
      (node (ref "E35") (pin "1") (pinfunction "A_1") (pintype "input"))
      (node (ref "E36") (pin "2") (pinfunction "Q1_2") (pintype "output"))
      (node (ref "J4") (pin "7") (pinfunction "7_7") (pintype "passive"))
    )
    (net (code "24") (name "DISPINH") (class "Default")
      (node (ref "E16") (pin "9") (pinfunction "Q_9") (pintype "output"))
      (node (ref "E22") (pin "12") (pinfunction "I1_12") (pintype "input"))
      (node (ref "J4") (pin "4") (pinfunction "4_4") (pintype "passive"))
    )
    (net (code "25") (name "DISPLAY0") (class "Default")
      (node (ref "E19") (pin "7") (pinfunction "1Y_7") (pintype "output"))
      (node (ref "J3") (pin "7") (pinfunction "7_7") (pintype "passive"))
    )
    (net (code "26") (name "DISPLAY1") (class "Default")
      (node (ref "E19") (pin "9") (pinfunction "2Y_9") (pintype "output"))
      (node (ref "J3") (pin "11") (pinfunction "11_11") (pintype "passive"))
    )
    (net (code "27") (name "DISPLAY2") (class "Default")
      (node (ref "E18") (pin "7") (pinfunction "1Y_7") (pintype "output"))
      (node (ref "J3") (pin "6") (pinfunction "6_6") (pintype "passive"))
    )
    (net (code "28") (name "E30PIN8") (class "Default")
      (node (ref "E21") (pin "11") (pinfunction "I2_11") (pintype "input"))
      (node (ref "E21") (pin "5") (pinfunction "I2_5") (pintype "input"))
      (node (ref "E30") (pin "8") (pinfunction "O_8") (pintype "output"))
    )
    (net (code "29") (name "ENT0") (class "Default")
      (node (ref "E11") (pin "8") (pinfunction "A4_8") (pintype "input"))
      (node (ref "E3") (pin "13") (pinfunction "QA_13") (pintype "output"))
      (node (ref "E36") (pin "14") (pinfunction "D6_14") (pintype "input"))
      (node (ref "E7") (pin "13") (pinfunction "D4_13") (pintype "input"))
    )
    (net (code "30") (name "ENT1") (class "Default")
      (node (ref "E10") (pin "8") (pinfunction "A4_8") (pintype "input"))
      (node (ref "E2") (pin "13") (pinfunction "QA_13") (pintype "output"))
      (node (ref "E36") (pin "4") (pinfunction "D2_4") (pintype "input"))
      (node (ref "E6") (pin "13") (pinfunction "D4_13") (pintype "input"))
    )
    (net (code "31") (name "ENT2") (class "Default")
      (node (ref "E1") (pin "13") (pinfunction "QA_13") (pintype "output"))
      (node (ref "E36") (pin "3") (pinfunction "D1_3") (pintype "input"))
      (node (ref "E5") (pin "13") (pinfunction "D4_13") (pintype "input"))
      (node (ref "E9") (pin "8") (pinfunction "A4_8") (pintype "input"))
    )
    (net (code "32") (name "GND") (class "Default")
      (node (ref "C1") (pin "2") (pinfunction "2_2") (pintype "passive"))
      (node (ref "C10") (pin "2") (pinfunction "2_2") (pintype "passive"))
      (node (ref "C11") (pin "2") (pinfunction "2_2") (pintype "passive"))
      (node (ref "C12") (pin "2") (pinfunction "2_2") (pintype "passive"))
      (node (ref "C13") (pin "2") (pinfunction "2_2") (pintype "passive"))
      (node (ref "C14") (pin "2") (pinfunction "2_2") (pintype "passive"))
      (node (ref "C15") (pin "2") (pinfunction "2_2") (pintype "passive"))
      (node (ref "C16") (pin "2") (pinfunction "2_2") (pintype "passive"))
      (node (ref "C17") (pin "2") (pinfunction "2_2") (pintype "passive"))
      (node (ref "C18") (pin "2") (pinfunction "2_2") (pintype "passive"))
      (node (ref "C19") (pin "2") (pinfunction "2_2") (pintype "passive"))
      (node (ref "C2") (pin "2") (pinfunction "2_2") (pintype "passive"))
      (node (ref "C20") (pin "2") (pinfunction "2_2") (pintype "passive"))
      (node (ref "C21") (pin "2") (pinfunction "2_2") (pintype "passive"))
      (node (ref "C22") (pin "2") (pinfunction "2_2") (pintype "passive"))
      (node (ref "C23") (pin "2") (pinfunction "2_2") (pintype "passive"))
      (node (ref "C24") (pin "2") (pinfunction "2_2") (pintype "passive"))
      (node (ref "C25") (pin "2") (pinfunction "2_2") (pintype "passive"))
      (node (ref "C26A") (pin "2") (pinfunction "2_2") (pintype "passive"))
      (node (ref "C27") (pin "2") (pinfunction "2_2") (pintype "passive"))
      (node (ref "C28") (pin "2") (pinfunction "2_2") (pintype "passive"))
      (node (ref "C29") (pin "2") (pinfunction "2_2") (pintype "passive"))
      (node (ref "C3") (pin "2") (pinfunction "2_2") (pintype "passive"))
      (node (ref "C30") (pin "2") (pinfunction "2_2") (pintype "passive"))
      (node (ref "C31") (pin "2") (pinfunction "2_2") (pintype "passive"))
      (node (ref "C32") (pin "2") (pinfunction "2_2") (pintype "passive"))
      (node (ref "C33") (pin "2") (pinfunction "2_2") (pintype "passive"))
      (node (ref "C34") (pin "2") (pinfunction "2_2") (pintype "passive"))
      (node (ref "C35") (pin "2") (pinfunction "2_2") (pintype "passive"))
      (node (ref "C36") (pin "2") (pinfunction "2_2") (pintype "passive"))
      (node (ref "C38") (pin "-") (pinfunction "-_-") (pintype "passive"))
      (node (ref "C39") (pin "-") (pinfunction "-_-") (pintype "passive"))
      (node (ref "C4") (pin "2") (pinfunction "2_2") (pintype "passive"))
      (node (ref "C5") (pin "2") (pinfunction "2_2") (pintype "passive"))
      (node (ref "C6") (pin "2") (pinfunction "2_2") (pintype "passive"))
      (node (ref "C7") (pin "2") (pinfunction "2_2") (pintype "passive"))
      (node (ref "C8") (pin "2") (pinfunction "2_2") (pintype "passive"))
      (node (ref "C9") (pin "2") (pinfunction "2_2") (pintype "passive"))
      (node (ref "E1") (pin "3") (pinfunction "B_3") (pintype "input"))
      (node (ref "E1") (pin "4") (pinfunction "C_4") (pintype "input"))
      (node (ref "E1") (pin "5") (pinfunction "D_5") (pintype "input"))
      (node (ref "E17") (pin "1") (pinfunction "1G_1") (pintype "input"))
      (node (ref "E17") (pin "15") (pinfunction "2G_15") (pintype "input"))
      (node (ref "E18") (pin "1") (pinfunction "1G_1") (pintype "input"))
      (node (ref "E18") (pin "15") (pinfunction "2G_15") (pintype "input"))
      (node (ref "E19") (pin "1") (pinfunction "1G_1") (pintype "input"))
      (node (ref "E19") (pin "15") (pinfunction "2G_15") (pintype "input"))
      (node (ref "E2") (pin "3") (pinfunction "B_3") (pintype "input"))
      (node (ref "E2") (pin "4") (pinfunction "C_4") (pintype "input"))
      (node (ref "E2") (pin "5") (pinfunction "D_5") (pintype "input"))
      (node (ref "E25") (pin "3") (pinfunction "I0_3") (pintype "input"))
      (node (ref "E25") (pin "4") (pinfunction "I1_4") (pintype "input"))
      (node (ref "E3") (pin "3") (pinfunction "B_3") (pintype "input"))
      (node (ref "E3") (pin "4") (pinfunction "C_4") (pintype "input"))
      (node (ref "E3") (pin "5") (pinfunction "D_5") (pintype "input"))
      (node (ref "GND") (pin "1") (pinfunction "P_1") (pintype "passive"))
      (node (ref "J1") (pin "11") (pinfunction "11_11") (pintype "passive"))
      (node (ref "J1") (pin "13") (pinfunction "13_13") (pintype "passive"))
      (node (ref "J1") (pin "15") (pinfunction "15_15") (pintype "passive"))
      (node (ref "J1") (pin "17") (pinfunction "17_17") (pintype "passive"))
      (node (ref "J1") (pin "19") (pinfunction "19_19") (pintype "passive"))
      (node (ref "J1") (pin "21") (pinfunction "21_21") (pintype "passive"))
      (node (ref "J1") (pin "23") (pinfunction "23_23") (pintype "passive"))
      (node (ref "J1") (pin "25") (pinfunction "25_25") (pintype "passive"))
      (node (ref "J1") (pin "27") (pinfunction "27_27") (pintype "passive"))
      (node (ref "J1") (pin "29") (pinfunction "29_29") (pintype "passive"))
      (node (ref "J1") (pin "31") (pinfunction "31_31") (pintype "passive"))
      (node (ref "J1") (pin "33") (pinfunction "33_33") (pintype "passive"))
      (node (ref "J1") (pin "35") (pinfunction "35_35") (pintype "passive"))
      (node (ref "J1") (pin "37") (pinfunction "37_37") (pintype "passive"))
      (node (ref "J1") (pin "39") (pinfunction "39_39") (pintype "passive"))
      (node (ref "J2") (pin "11") (pinfunction "11_11") (pintype "passive"))
      (node (ref "J2") (pin "13") (pinfunction "13_13") (pintype "passive"))
      (node (ref "J2") (pin "15") (pinfunction "15_15") (pintype "passive"))
      (node (ref "J2") (pin "16") (pinfunction "16_16") (pintype "passive"))
      (node (ref "J2") (pin "17") (pinfunction "17_17") (pintype "passive"))
      (node (ref "J2") (pin "19") (pinfunction "19_19") (pintype "passive"))
      (node (ref "J2") (pin "21") (pinfunction "21_21") (pintype "passive"))
      (node (ref "J2") (pin "23") (pinfunction "23_23") (pintype "passive"))
      (node (ref "J2") (pin "25") (pinfunction "25_25") (pintype "passive"))
      (node (ref "J2") (pin "27") (pinfunction "27_27") (pintype "passive"))
      (node (ref "J2") (pin "29") (pinfunction "29_29") (pintype "passive"))
      (node (ref "J2") (pin "31") (pinfunction "31_31") (pintype "passive"))
      (node (ref "J2") (pin "33") (pinfunction "33_33") (pintype "passive"))
      (node (ref "J2") (pin "35") (pinfunction "35_35") (pintype "passive"))
      (node (ref "J2") (pin "37") (pinfunction "37_37") (pintype "passive"))
      (node (ref "J2") (pin "39") (pinfunction "39_39") (pintype "passive"))
      (node (ref "J3") (pin "8") (pinfunction "8_8") (pintype "passive"))
      (node (ref "J4") (pin "8") (pinfunction "8_8") (pintype "passive"))
      (node (ref "R1") (pin "1") (pinfunction "1_1") (pintype "passive"))
      (node (ref "R17") (pin "1") (pinfunction "1_1") (pintype "passive"))
      (node (ref "R18") (pin "1") (pinfunction "1_1") (pintype "passive"))
      (node (ref "R19") (pin "1") (pinfunction "1_1") (pintype "passive"))
      (node (ref "R2") (pin "1") (pinfunction "1_1") (pintype "passive"))
      (node (ref "R20") (pin "1") (pinfunction "1_1") (pintype "passive"))
      (node (ref "R21") (pin "1") (pinfunction "1_1") (pintype "passive"))
      (node (ref "R22") (pin "1") (pinfunction "1_1") (pintype "passive"))
      (node (ref "R23") (pin "1") (pinfunction "1_1") (pintype "passive"))
      (node (ref "R24") (pin "1") (pinfunction "1_1") (pintype "passive"))
      (node (ref "R27") (pin "1") (pinfunction "1_1") (pintype "passive"))
      (node (ref "R3") (pin "1") (pinfunction "1_1") (pintype "passive"))
      (node (ref "R30") (pin "1") (pinfunction "1_1") (pintype "passive"))
      (node (ref "R4") (pin "1") (pinfunction "1_1") (pintype "passive"))
    )
    (net (code "33") (name "KEYSTB") (class "Default")
      (node (ref "E24") (pin "1") (pinfunction "I_1") (pintype "input"))
      (node (ref "E8") (pin "5") (pinfunction "I1_5") (pintype "input"))
      (node (ref "J4") (pin "2") (pinfunction "2_2") (pintype "passive"))
    )
    (net (code "34") (name "LDSR") (class "Default")
      (node (ref "E33") (pin "13") (pinfunction "O_13") (pintype "output"))
      (node (ref "E5") (pin "9") (pinfunction "CLK_9") (pintype "input"))
      (node (ref "E6") (pin "9") (pinfunction "CLK_9") (pintype "input"))
      (node (ref "E7") (pin "9") (pinfunction "CLK_9") (pintype "input"))
    )
    (net (code "35") (name "MH0") (class "Default")
      (node (ref "E20") (pin "9") (pinfunction "Q_9") (pintype "output"))
      (node (ref "E22") (pin "11") (pinfunction "I0_11") (pintype "input"))
      (node (ref "E8") (pin "13") (pinfunction "I1_13") (pintype "input"))
    )
    (net (code "36") (name "MPXA") (class "Default")
      (node (ref "E17") (pin "14") (pinfunction "A_14") (pintype "input"))
      (node (ref "E18") (pin "14") (pinfunction "A_14") (pintype "input"))
      (node (ref "E19") (pin "14") (pinfunction "A_14") (pintype "input"))
      (node (ref "J4") (pin "14") (pinfunction "14_14") (pintype "passive"))
    )
    (net (code "37") (name "MPXB") (class "Default")
      (node (ref "E17") (pin "2") (pinfunction "B_2") (pintype "input"))
      (node (ref "E18") (pin "2") (pinfunction "B_2") (pintype "input"))
      (node (ref "E19") (pin "2") (pinfunction "B_2") (pintype "input"))
      (node (ref "J4") (pin "13") (pinfunction "13_13") (pintype "passive"))
    )
    (net (code "38") (name "NUM") (class "Default")
      (node (ref "E16") (pin "12") (pinfunction "D_12") (pintype "input"))
      (node (ref "E21") (pin "13") (pinfunction "I2_13") (pintype "input"))
      (node (ref "E8") (pin "4") (pinfunction "I0_4") (pintype "input"))
      (node (ref "J4") (pin "11") (pinfunction "11_11") (pintype "passive"))
    )
    (net (code "39") (name "NUMCLK") (class "Default")
      (node (ref "E1") (pin "8") (pinfunction "CK2_8") (pintype "input"))
      (node (ref "E1") (pin "9") (pinfunction "CK1_9") (pintype "input"))
      (node (ref "E2") (pin "8") (pinfunction "CK2_8") (pintype "input"))
      (node (ref "E2") (pin "9") (pinfunction "CK1_9") (pintype "input"))
      (node (ref "E3") (pin "8") (pinfunction "CK2_8") (pintype "input"))
      (node (ref "E3") (pin "9") (pinfunction "CK1_9") (pintype "input"))
      (node (ref "E8") (pin "6") (pinfunction "O_6") (pintype "output"))
    )
    (net (code "40") (name "Net-(E1A-QB)") (class "Default")
      (node (ref "E1") (pin "12") (pinfunction "QB_12") (pintype "output"))
      (node (ref "E5") (pin "12") (pinfunction "D3_12") (pintype "input"))
      (node (ref "E9") (pin "6") (pinfunction "A3_6") (pintype "input"))
    )
    (net (code "41") (name "Net-(E1A-QC)") (class "Default")
      (node (ref "E1") (pin "11") (pinfunction "QC_11") (pintype "output"))
      (node (ref "E5") (pin "5") (pinfunction "D2_5") (pintype "input"))
      (node (ref "E9") (pin "4") (pinfunction "A2_4") (pintype "input"))
    )
    (net (code "42") (name "Net-(E1A-QD)") (class "Default")
      (node (ref "E1") (pin "10") (pinfunction "QD_10") (pintype "output"))
      (node (ref "E5") (pin "4") (pinfunction "D1_4") (pintype "input"))
      (node (ref "E9") (pin "2") (pinfunction "A1_2") (pintype "input"))
    )
    (net (code "43") (name "Net-(E4B-C)") (class "Default")
      (node (ref "C37") (pin "2") (pinfunction "2_2") (pintype "passive"))
      (node (ref "C40") (pin "2") (pinfunction "2_2") (pintype "passive"))
      (node (ref "E4") (pin "6") (pinfunction "C_6") (pintype "input"))
    )
    (net (code "44") (name "Net-(E4B-Q)") (class "Default")
      (node (ref "E4") (pin "5") (pinfunction "Q_5") (pintype "output"))
      (node (ref "E8") (pin "10") (pinfunction "I1_10") (pintype "input"))
      (node (ref "E8") (pin "12") (pinfunction "I0_12") (pintype "input"))
    )
    (net (code "45") (name "Net-(E4B-R{slash}C)") (class "Default")
      (node (ref "C37") (pin "1") (pinfunction "1_1") (pintype "passive"))
      (node (ref "C40") (pin "1") (pinfunction "1_1") (pintype "passive"))
      (node (ref "E4") (pin "7") (pinfunction "R/C_7") (pintype "input"))
      (node (ref "R25") (pin "2") (pinfunction "2_2") (pintype "passive"))
    )
    (net (code "46") (name "Net-(E5A-Q1)") (class "Default")
      (node (ref "E5") (pin "2") (pinfunction "Q1_2") (pintype "output"))
      (node (ref "E9") (pin "17") (pinfunction "A4_17") (pintype "input"))
    )
    (net (code "47") (name "Net-(E5A-Q2)") (class "Default")
      (node (ref "E5") (pin "7") (pinfunction "Q2_7") (pintype "output"))
      (node (ref "E9") (pin "15") (pinfunction "A3_15") (pintype "input"))
    )
    (net (code "48") (name "Net-(E5A-Q3)") (class "Default")
      (node (ref "E5") (pin "10") (pinfunction "Q3_10") (pintype "output"))
      (node (ref "E9") (pin "13") (pinfunction "A2_13") (pintype "input"))
    )
    (net (code "49") (name "Net-(E5A-Q4)") (class "Default")
      (node (ref "E5") (pin "15") (pinfunction "Q4_15") (pintype "output"))
      (node (ref "E9") (pin "11") (pinfunction "A1_11") (pintype "input"))
    )
    (net (code "50") (name "Net-(E10A-A1)") (class "Default")
      (node (ref "E10") (pin "2") (pinfunction "A1_2") (pintype "input"))
      (node (ref "E2") (pin "10") (pinfunction "QD_10") (pintype "output"))
      (node (ref "E6") (pin "4") (pinfunction "D1_4") (pintype "input"))
    )
    (net (code "51") (name "Net-(E10A-A2)") (class "Default")
      (node (ref "E10") (pin "4") (pinfunction "A2_4") (pintype "input"))
      (node (ref "E2") (pin "11") (pinfunction "QC_11") (pintype "output"))
      (node (ref "E6") (pin "5") (pinfunction "D2_5") (pintype "input"))
    )
    (net (code "52") (name "Net-(E10A-A3)") (class "Default")
      (node (ref "E10") (pin "6") (pinfunction "A3_6") (pintype "input"))
      (node (ref "E2") (pin "12") (pinfunction "QB_12") (pintype "output"))
      (node (ref "E6") (pin "12") (pinfunction "D3_12") (pintype "input"))
    )
    (net (code "53") (name "Net-(E10B-A1)") (class "Default")
      (node (ref "E10") (pin "11") (pinfunction "A1_11") (pintype "input"))
      (node (ref "E6") (pin "15") (pinfunction "Q4_15") (pintype "output"))
    )
    (net (code "54") (name "Net-(E10B-A2)") (class "Default")
      (node (ref "E10") (pin "13") (pinfunction "A2_13") (pintype "input"))
      (node (ref "E6") (pin "10") (pinfunction "Q3_10") (pintype "output"))
    )
    (net (code "55") (name "Net-(E10B-A3)") (class "Default")
      (node (ref "E10") (pin "15") (pinfunction "A3_15") (pintype "input"))
      (node (ref "E6") (pin "7") (pinfunction "Q2_7") (pintype "output"))
    )
    (net (code "56") (name "Net-(E10B-A4)") (class "Default")
      (node (ref "E10") (pin "17") (pinfunction "A4_17") (pintype "input"))
      (node (ref "E6") (pin "2") (pinfunction "Q1_2") (pintype "output"))
    )
    (net (code "57") (name "Net-(E11A-A1)") (class "Default")
      (node (ref "E11") (pin "2") (pinfunction "A1_2") (pintype "input"))
      (node (ref "E3") (pin "10") (pinfunction "QD_10") (pintype "output"))
      (node (ref "E7") (pin "4") (pinfunction "D1_4") (pintype "input"))
    )
    (net (code "58") (name "Net-(E11A-A2)") (class "Default")
      (node (ref "E11") (pin "4") (pinfunction "A2_4") (pintype "input"))
      (node (ref "E3") (pin "11") (pinfunction "QC_11") (pintype "output"))
      (node (ref "E7") (pin "5") (pinfunction "D2_5") (pintype "input"))
    )
    (net (code "59") (name "Net-(E11A-A3)") (class "Default")
      (node (ref "E11") (pin "6") (pinfunction "A3_6") (pintype "input"))
      (node (ref "E3") (pin "12") (pinfunction "QB_12") (pintype "output"))
      (node (ref "E7") (pin "12") (pinfunction "D3_12") (pintype "input"))
    )
    (net (code "60") (name "Net-(E11B-A1)") (class "Default")
      (node (ref "E11") (pin "11") (pinfunction "A1_11") (pintype "input"))
      (node (ref "E7") (pin "15") (pinfunction "Q4_15") (pintype "output"))
    )
    (net (code "61") (name "Net-(E11B-A2)") (class "Default")
      (node (ref "E11") (pin "13") (pinfunction "A2_13") (pintype "input"))
      (node (ref "E7") (pin "10") (pinfunction "Q3_10") (pintype "output"))
    )
    (net (code "62") (name "Net-(E11B-A3)") (class "Default")
      (node (ref "E11") (pin "15") (pinfunction "A3_15") (pintype "input"))
      (node (ref "E7") (pin "7") (pinfunction "Q2_7") (pintype "output"))
    )
    (net (code "63") (name "Net-(E11B-A4)") (class "Default")
      (node (ref "E11") (pin "17") (pinfunction "A4_17") (pintype "input"))
      (node (ref "E7") (pin "2") (pinfunction "Q1_2") (pintype "output"))
    )
    (net (code "64") (name "Net-(E12A-Q1)") (class "Default")
      (node (ref "E12") (pin "2") (pinfunction "Q1_2") (pintype "output"))
      (node (ref "E17") (pin "4") (pinfunction "1C2_4") (pintype "input"))
    )
    (net (code "65") (name "Net-(E12A-Q2)") (class "Default")
      (node (ref "E12") (pin "5") (pinfunction "Q2_5") (pintype "output"))
      (node (ref "E17") (pin "6") (pinfunction "1C0_6") (pintype "input"))
    )
    (net (code "66") (name "Net-(E12A-Q3)") (class "Default")
      (node (ref "E12") (pin "7") (pinfunction "Q3_7") (pintype "output"))
      (node (ref "E17") (pin "13") (pinfunction "2C3_13") (pintype "input"))
    )
    (net (code "67") (name "Net-(E12A-Q4)") (class "Default")
      (node (ref "E12") (pin "10") (pinfunction "Q4_10") (pintype "output"))
      (node (ref "E17") (pin "11") (pinfunction "2C1_11") (pintype "input"))
    )
    (net (code "68") (name "Net-(E12A-Q5)") (class "Default")
      (node (ref "E12") (pin "12") (pinfunction "Q5_12") (pintype "output"))
      (node (ref "E17") (pin "12") (pinfunction "2C2_12") (pintype "input"))
    )
    (net (code "69") (name "Net-(E12A-Q6)") (class "Default")
      (node (ref "E12") (pin "15") (pinfunction "Q6_15") (pintype "output"))
      (node (ref "E17") (pin "10") (pinfunction "2C0_10") (pintype "input"))
    )
    (net (code "70") (name "Net-(E13A-Q1)") (class "Default")
      (node (ref "E13") (pin "2") (pinfunction "Q1_2") (pintype "output"))
      (node (ref "E19") (pin "12") (pinfunction "2C2_12") (pintype "input"))
    )
    (net (code "71") (name "Net-(E13A-Q2)") (class "Default")
      (node (ref "E13") (pin "5") (pinfunction "Q2_5") (pintype "output"))
      (node (ref "E19") (pin "10") (pinfunction "2C0_10") (pintype "input"))
    )
    (net (code "72") (name "Net-(E13A-Q3)") (class "Default")
      (node (ref "E13") (pin "7") (pinfunction "Q3_7") (pintype "output"))
      (node (ref "E18") (pin "3") (pinfunction "1C3_3") (pintype "input"))
    )
    (net (code "73") (name "Net-(E13A-Q4)") (class "Default")
      (node (ref "E13") (pin "10") (pinfunction "Q4_10") (pintype "output"))
      (node (ref "E18") (pin "5") (pinfunction "1C1_5") (pintype "input"))
    )
    (net (code "74") (name "Net-(E13A-Q5)") (class "Default")
      (node (ref "E13") (pin "12") (pinfunction "Q5_12") (pintype "output"))
      (node (ref "E18") (pin "4") (pinfunction "1C2_4") (pintype "input"))
    )
    (net (code "75") (name "Net-(E13A-Q6)") (class "Default")
      (node (ref "E13") (pin "15") (pinfunction "Q6_15") (pintype "output"))
      (node (ref "E18") (pin "6") (pinfunction "1C0_6") (pintype "input"))
    )
    (net (code "76") (name "Net-(E14A-Q1)") (class "Default")
      (node (ref "E14") (pin "2") (pinfunction "Q1_2") (pintype "output"))
      (node (ref "E18") (pin "13") (pinfunction "2C3_13") (pintype "input"))
    )
    (net (code "77") (name "Net-(E14A-Q2)") (class "Default")
      (node (ref "E14") (pin "5") (pinfunction "Q2_5") (pintype "output"))
      (node (ref "E18") (pin "11") (pinfunction "2C1_11") (pintype "input"))
    )
    (net (code "78") (name "Net-(E14A-Q3)") (class "Default")
      (node (ref "E14") (pin "7") (pinfunction "Q3_7") (pintype "output"))
      (node (ref "E18") (pin "12") (pinfunction "2C2_12") (pintype "input"))
    )
    (net (code "79") (name "Net-(E14A-Q4)") (class "Default")
      (node (ref "E14") (pin "10") (pinfunction "Q4_10") (pintype "output"))
      (node (ref "E18") (pin "10") (pinfunction "2C0_10") (pintype "input"))
    )
    (net (code "80") (name "Net-(E14A-Q5)") (class "Default")
      (node (ref "E14") (pin "12") (pinfunction "Q5_12") (pintype "output"))
      (node (ref "E17") (pin "3") (pinfunction "1C3_3") (pintype "input"))
    )
    (net (code "81") (name "Net-(E14A-Q6)") (class "Default")
      (node (ref "E14") (pin "15") (pinfunction "Q6_15") (pintype "output"))
      (node (ref "E17") (pin "5") (pinfunction "1C1_5") (pintype "input"))
    )
    (net (code "82") (name "Net-(E15A-Q1)") (class "Default")
      (node (ref "E15") (pin "2") (pinfunction "Q1_2") (pintype "output"))
      (node (ref "E19") (pin "3") (pinfunction "1C3_3") (pintype "input"))
    )
    (net (code "83") (name "Net-(E15A-Q2)") (class "Default")
      (node (ref "E15") (pin "5") (pinfunction "Q2_5") (pintype "output"))
      (node (ref "E19") (pin "5") (pinfunction "1C1_5") (pintype "input"))
    )
    (net (code "84") (name "Net-(E15A-Q3)") (class "Default")
      (node (ref "E15") (pin "7") (pinfunction "Q3_7") (pintype "output"))
      (node (ref "E19") (pin "4") (pinfunction "1C2_4") (pintype "input"))
    )
    (net (code "85") (name "Net-(E15A-Q4)") (class "Default")
      (node (ref "E15") (pin "10") (pinfunction "Q4_10") (pintype "output"))
      (node (ref "E19") (pin "6") (pinfunction "1C0_6") (pintype "input"))
    )
    (net (code "86") (name "Net-(E15A-Q5)") (class "Default")
      (node (ref "E15") (pin "12") (pinfunction "Q5_12") (pintype "output"))
      (node (ref "E19") (pin "13") (pinfunction "2C3_13") (pintype "input"))
    )
    (net (code "87") (name "Net-(E15A-Q6)") (class "Default")
      (node (ref "E15") (pin "15") (pinfunction "Q6_15") (pintype "output"))
      (node (ref "E19") (pin "11") (pinfunction "2C1_11") (pintype "input"))
    )
    (net (code "88") (name "Net-(E16A-CLK)") (class "Default")
      (node (ref "E16") (pin "3") (pinfunction "CLK_3") (pintype "input"))
      (node (ref "E21") (pin "12") (pinfunction "O_12") (pintype "output"))
    )
    (net (code "89") (name "Net-(E20A-PRE)") (class "Default")
      (node (ref "E20") (pin "4") (pinfunction "PRE_4") (pintype "input"))
      (node (ref "E26") (pin "8") (pinfunction "~{Q4}_8") (pintype "output"))
    )
    (net (code "90") (name "Net-(E20B-CLK)") (class "Default")
      (node (ref "E20") (pin "11") (pinfunction "CLK_11") (pintype "input"))
      (node (ref "E22") (pin "1") (pinfunction "O_1") (pintype "output"))
      (node (ref "E4") (pin "9") (pinfunction "A_9") (pintype "input"))
    )
    (net (code "91") (name "Net-(E21A-I0)") (class "Default")
      (node (ref "E21") (pin "1") (pinfunction "I0_1") (pintype "input"))
      (node (ref "E24") (pin "4") (pinfunction "O_4") (pintype "output"))
    )
    (net (code "92") (name "Net-(E21B-I0)") (class "Default")
      (node (ref "E21") (pin "3") (pinfunction "I0_3") (pintype "input"))
      (node (ref "E21") (pin "4") (pinfunction "I1_4") (pintype "input"))
      (node (ref "E22") (pin "4") (pinfunction "O_4") (pintype "output"))
    )
    (net (code "93") (name "Net-(E21C-O)") (class "Default")
      (node (ref "E21") (pin "8") (pinfunction "O_8") (pintype "output"))
      (node (ref "E23") (pin "9") (pinfunction "I_9") (pintype "input"))
    )
    (net (code "94") (name "Net-(E22A-I0)") (class "Default")
      (node (ref "E22") (pin "2") (pinfunction "I0_2") (pintype "input"))
      (node (ref "E32") (pin "6") (pinfunction "O_6") (pintype "output"))
    )
    (net (code "95") (name "Net-(E22A-I1)") (class "Default")
      (node (ref "E22") (pin "3") (pinfunction "I1_3") (pintype "input"))
      (node (ref "E33") (pin "1") (pinfunction "O_1") (pintype "output"))
    )
    (net (code "96") (name "Net-(E22B-I0)") (class "Default")
      (node (ref "E22") (pin "5") (pinfunction "I0_5") (pintype "input"))
      (node (ref "E8") (pin "3") (pinfunction "O_3") (pintype "output"))
    )
    (net (code "97") (name "Net-(E22C-I0)") (class "Default")
      (node (ref "E22") (pin "8") (pinfunction "I0_8") (pintype "input"))
      (node (ref "E25") (pin "12") (pinfunction "O_12") (pintype "output"))
    )
    (net (code "98") (name "Net-(E22C-I1)") (class "Default")
      (node (ref "E22") (pin "9") (pinfunction "I1_9") (pintype "input"))
      (node (ref "E25") (pin "8") (pinfunction "O_8") (pintype "output"))
    )
    (net (code "99") (name "Net-(E22C-O)") (class "Default")
      (node (ref "E22") (pin "10") (pinfunction "O_10") (pintype "output"))
      (node (ref "E29") (pin "4") (pinfunction "G2A_4") (pintype "input"))
      (node (ref "E29") (pin "5") (pinfunction "G2B_5") (pintype "input"))
      (node (ref "E31") (pin "15") (pinfunction "2G_15") (pintype "input"))
    )
    (net (code "100") (name "Net-(E22D-O)") (class "Default")
      (node (ref "E22") (pin "13") (pinfunction "O_13") (pintype "output"))
      (node (ref "E30") (pin "4") (pinfunction "I0_4") (pintype "input"))
    )
    (net (code "101") (name "Net-(E23A-I)") (class "Default")
      (node (ref "E23") (pin "1") (pinfunction "I_1") (pintype "input"))
      (node (ref "E33") (pin "4") (pinfunction "O_4") (pintype "output"))
    )
    (net (code "102") (name "Net-(E23E-I)") (class "Default")
      (node (ref "E23") (pin "11") (pinfunction "I_11") (pintype "input"))
      (node (ref "E24") (pin "10") (pinfunction "O_10") (pintype "output"))
    )
    (net (code "103") (name "Net-(E23F-I)") (class "Default")
      (node (ref "E23") (pin "13") (pinfunction "I_13") (pintype "input"))
      (node (ref "E25") (pin "6") (pinfunction "O_6") (pintype "output"))
    )
    (net (code "104") (name "Net-(E24D-O)") (class "Default")
      (node (ref "E24") (pin "8") (pinfunction "O_8") (pintype "output"))
      (node (ref "E32") (pin "5") (pinfunction "I1_5") (pintype "input"))
    )
    (net (code "105") (name "Net-(E24F-O)") (class "Default")
      (node (ref "E24") (pin "12") (pinfunction "O_12") (pintype "output"))
      (node (ref "E25") (pin "10") (pinfunction "I1_10") (pintype "input"))
      (node (ref "E28") (pin "1") (pinfunction "1G_1") (pintype "input"))
      (node (ref "E28") (pin "15") (pinfunction "2G_15") (pintype "input"))
      (node (ref "E33") (pin "6") (pinfunction "I1_6") (pintype "input"))
    )
    (net (code "106") (name "Net-(E25A-I0)") (class "Default")
      (node (ref "E25") (pin "1") (pinfunction "I0_1") (pintype "input"))
      (node (ref "E26") (pin "16") (pinfunction "Q1_16") (pintype "output"))
      (node (ref "E29") (pin "3") (pinfunction "C_3") (pintype "input"))
    )
    (net (code "107") (name "Net-(E25A-I2)") (class "Default")
      (node (ref "E25") (pin "13") (pinfunction "I2_13") (pintype "input"))
      (node (ref "E26") (pin "15") (pinfunction "Q2_15") (pintype "output"))
      (node (ref "E27") (pin "3") (pinfunction "I_3") (pintype "input"))
      (node (ref "E29") (pin "2") (pinfunction "B_2") (pintype "input"))
      (node (ref "E30") (pin "1") (pinfunction "I0_1") (pintype "input"))
    )
    (net (code "108") (name "Net-(E25B-I2)") (class "Default")
      (node (ref "D1") (pin "A") (pinfunction "A_A") (pintype "passive"))
      (node (ref "D2") (pin "A") (pinfunction "A_A") (pintype "passive"))
      (node (ref "E25") (pin "5") (pinfunction "I2_5") (pintype "input"))
      (node (ref "R37") (pin "1") (pinfunction "1_1") (pintype "passive"))
    )
    (net (code "109") (name "Net-(E25C-I0)") (class "Default")
      (node (ref "E25") (pin "9") (pinfunction "I0_9") (pintype "input"))
      (node (ref "E26") (pin "9") (pinfunction "Q4_9") (pintype "output"))
    )
    (net (code "110") (name "Net-(E26A-Q3)") (class "Default")
      (node (ref "E26") (pin "10") (pinfunction "Q3_10") (pintype "output"))
      (node (ref "E29") (pin "1") (pinfunction "A_1") (pintype "input"))
    )
    (net (code "111") (name "Net-(E27A-O)") (class "Default")
      (node (ref "E27") (pin "2") (pinfunction "O_2") (pintype "output"))
      (node (ref "E30") (pin "12") (pinfunction "I0_12") (pintype "input"))
    )
    (net (code "112") (name "Net-(E27B-O)") (class "Default")
      (node (ref "E27") (pin "4") (pinfunction "O_4") (pintype "output"))
      (node (ref "E31") (pin "12") (pinfunction "2A1_12") (pintype "input"))
    )
    (net (code "113") (name "Net-(E27C-O)") (class "Default")
      (node (ref "E27") (pin "6") (pinfunction "O_6") (pintype "output"))
      (node (ref "E30") (pin "13") (pinfunction "I1_13") (pintype "input"))
    )
    (net (code "114") (name "Net-(E28A-1A1)") (class "Default")
      (node (ref "E28") (pin "2") (pinfunction "1A1_2") (pintype "input"))
      (node (ref "E29") (pin "9") (pinfunction "Y6_9") (pintype "output"))
      (node (ref "E32") (pin "2") (pinfunction "I1_2") (pintype "input"))
    )
    (net (code "115") (name "Net-(E28A-1A2)") (class "Default")
      (node (ref "E28") (pin "4") (pinfunction "1A2_4") (pintype "input"))
      (node (ref "E29") (pin "7") (pinfunction "Y7_7") (pintype "output"))
      (node (ref "E30") (pin "10") (pinfunction "I1_10") (pintype "input"))
      (node (ref "E32") (pin "1") (pinfunction "I0_1") (pintype "input"))
    )
    (net (code "116") (name "Net-(E28A-1A3)") (class "Default")
      (node (ref "E28") (pin "6") (pinfunction "1A3_6") (pintype "input"))
      (node (ref "E30") (pin "9") (pinfunction "I0_9") (pintype "input"))
      (node (ref "E31") (pin "6") (pinfunction "1A3_6") (pintype "input"))
      (node (ref "E32") (pin "8") (pinfunction "O_8") (pintype "output"))
      (node (ref "E33") (pin "5") (pinfunction "I0_5") (pintype "input"))
    )
    (net (code "117") (name "Net-(E28A-2A2)") (class "Default")
      (node (ref "E28") (pin "14") (pinfunction "2A2_14") (pintype "input"))
      (node (ref "E30") (pin "11") (pinfunction "O_11") (pintype "output"))
    )
    (net (code "118") (name "Net-(E29A-Y0)") (class "Default")
      (node (ref "E29") (pin "15") (pinfunction "Y0_15") (pintype "output"))
      (node (ref "E33") (pin "8") (pinfunction "I0_8") (pintype "input"))
    )
    (net (code "119") (name "Net-(E29A-Y1)") (class "Default")
      (node (ref "E29") (pin "14") (pinfunction "Y1_14") (pintype "output"))
      (node (ref "E33") (pin "12") (pinfunction "I1_12") (pintype "input"))
    )
    (net (code "120") (name "Net-(E29A-Y2)") (class "Default")
      (node (ref "E29") (pin "13") (pinfunction "Y2_13") (pintype "output"))
      (node (ref "E30") (pin "2") (pinfunction "I1_2") (pintype "input"))
      (node (ref "E32") (pin "10") (pinfunction "I1_10") (pintype "input"))
    )
    (net (code "121") (name "Net-(E29A-Y3)") (class "Default")
      (node (ref "E29") (pin "12") (pinfunction "Y3_12") (pintype "output"))
      (node (ref "E32") (pin "9") (pinfunction "I0_9") (pintype "input"))
    )
    (net (code "122") (name "Net-(E29A-Y4)") (class "Default")
      (node (ref "E29") (pin "11") (pinfunction "Y4_11") (pintype "output"))
      (node (ref "E31") (pin "10") (pinfunction "1A4_10") (pintype "input"))
    )
    (net (code "123") (name "Net-(E29A-Y5)") (class "Default")
      (node (ref "E29") (pin "10") (pinfunction "Y5_10") (pintype "output"))
      (node (ref "E31") (pin "2") (pinfunction "1A1_2") (pintype "input"))
    )
    (net (code "124") (name "Net-(E30A-O)") (class "Default")
      (node (ref "E30") (pin "3") (pinfunction "O_3") (pintype "output"))
      (node (ref "E31") (pin "14") (pinfunction "2A2_14") (pintype "input"))
    )
    (net (code "125") (name "Net-(E30B-O)") (class "Default")
      (node (ref "E30") (pin "6") (pinfunction "O_6") (pintype "output"))
      (node (ref "E34") (pin "1") (pinfunction "1G_1") (pintype "input"))
      (node (ref "E34") (pin "15") (pinfunction "2G_15") (pintype "input"))
      (node (ref "E35") (pin "4") (pinfunction "G2A_4") (pintype "input"))
      (node (ref "E35") (pin "5") (pinfunction "G2B_5") (pintype "input"))
    )
    (net (code "126") (name "Net-(E31A-1A2)") (class "Default")
      (node (ref "E31") (pin "4") (pinfunction "1A2_4") (pintype "input"))
      (node (ref "E32") (pin "3") (pinfunction "O_3") (pintype "output"))
    )
    (net (code "127") (name "Net-(E31A-1Y1)") (class "Default")
      (node (ref "D2") (pin "C") (pinfunction "C_C") (pintype "passive"))
      (node (ref "E31") (pin "3") (pinfunction "1Y1_3") (pintype "tri_state"))
    )
    (net (code "128") (name "Net-(E31A-1Y2)") (class "Default")
      (node (ref "D1") (pin "C") (pinfunction "C_C") (pintype "passive"))
      (node (ref "E31") (pin "5") (pinfunction "1Y2_5") (pintype "tri_state"))
    )
    (net (code "129") (name "Net-(E32D-I0)") (class "Default")
      (node (ref "E32") (pin "12") (pinfunction "I0_12") (pintype "input"))
      (node (ref "E35") (pin "11") (pinfunction "Y4_11") (pintype "output"))
    )
    (net (code "130") (name "Net-(E33C-O)") (class "Default")
      (node (ref "E33") (pin "10") (pinfunction "O_10") (pintype "output"))
      (node (ref "E36") (pin "9") (pinfunction "CLK_9") (pintype "input"))
    )
    (net (code "131") (name "Net-(E34A-1A3)") (class "Default")
      (node (ref "E34") (pin "6") (pinfunction "1A3_6") (pintype "input"))
      (node (ref "E35") (pin "9") (pinfunction "Y6_9") (pintype "output"))
    )
    (net (code "132") (name "Net-(E34A-2A1)") (class "Default")
      (node (ref "E34") (pin "12") (pinfunction "2A1_12") (pintype "input"))
      (node (ref "E35") (pin "10") (pinfunction "Y5_10") (pintype "output"))
    )
    (net (code "133") (name "POWCK") (class "Default")
      (node (ref "E24") (pin "11") (pinfunction "I_11") (pintype "input"))
      (node (ref "J2") (pin "28") (pinfunction "28_28") (pintype "passive"))
      (node (ref "R33") (pin "1") (pinfunction "1_1") (pintype "passive"))
    )
    (net (code "134") (name "THIS") (class "Default")
      (node (ref "E20") (pin "5") (pinfunction "Q_5") (pintype "output"))
      (node (ref "E28") (pin "12") (pinfunction "2A1_12") (pintype "input"))
    )
    (net (code "135") (name "VCC") (class "Default")
      (node (ref "C1") (pin "1") (pinfunction "1_1") (pintype "passive"))
      (node (ref "C10") (pin "1") (pinfunction "1_1") (pintype "passive"))
      (node (ref "C11") (pin "1") (pinfunction "1_1") (pintype "passive"))
      (node (ref "C12") (pin "1") (pinfunction "1_1") (pintype "passive"))
      (node (ref "C13") (pin "1") (pinfunction "1_1") (pintype "passive"))
      (node (ref "C14") (pin "1") (pinfunction "1_1") (pintype "passive"))
      (node (ref "C15") (pin "1") (pinfunction "1_1") (pintype "passive"))
      (node (ref "C16") (pin "1") (pinfunction "1_1") (pintype "passive"))
      (node (ref "C17") (pin "1") (pinfunction "1_1") (pintype "passive"))
      (node (ref "C18") (pin "1") (pinfunction "1_1") (pintype "passive"))
      (node (ref "C19") (pin "1") (pinfunction "1_1") (pintype "passive"))
      (node (ref "C2") (pin "1") (pinfunction "1_1") (pintype "passive"))
      (node (ref "C20") (pin "1") (pinfunction "1_1") (pintype "passive"))
      (node (ref "C21") (pin "1") (pinfunction "1_1") (pintype "passive"))
      (node (ref "C22") (pin "1") (pinfunction "1_1") (pintype "passive"))
      (node (ref "C23") (pin "1") (pinfunction "1_1") (pintype "passive"))
      (node (ref "C24") (pin "1") (pinfunction "1_1") (pintype "passive"))
      (node (ref "C25") (pin "1") (pinfunction "1_1") (pintype "passive"))
      (node (ref "C26A") (pin "1") (pinfunction "1_1") (pintype "passive"))
      (node (ref "C27") (pin "1") (pinfunction "1_1") (pintype "passive"))
      (node (ref "C28") (pin "1") (pinfunction "1_1") (pintype "passive"))
      (node (ref "C29") (pin "1") (pinfunction "1_1") (pintype "passive"))
      (node (ref "C3") (pin "1") (pinfunction "1_1") (pintype "passive"))
      (node (ref "C30") (pin "1") (pinfunction "1_1") (pintype "passive"))
      (node (ref "C31") (pin "1") (pinfunction "1_1") (pintype "passive"))
      (node (ref "C32") (pin "1") (pinfunction "1_1") (pintype "passive"))
      (node (ref "C33") (pin "1") (pinfunction "1_1") (pintype "passive"))
      (node (ref "C34") (pin "1") (pinfunction "1_1") (pintype "passive"))
      (node (ref "C35") (pin "1") (pinfunction "1_1") (pintype "passive"))
      (node (ref "C36") (pin "1") (pinfunction "1_1") (pintype "passive"))
      (node (ref "C38") (pin "+") (pinfunction "+_+") (pintype "passive"))
      (node (ref "C39") (pin "+") (pinfunction "+_+") (pintype "passive"))
      (node (ref "C4") (pin "1") (pinfunction "1_1") (pintype "passive"))
      (node (ref "C5") (pin "1") (pinfunction "1_1") (pintype "passive"))
      (node (ref "C6") (pin "1") (pinfunction "1_1") (pintype "passive"))
      (node (ref "C7") (pin "1") (pinfunction "1_1") (pintype "passive"))
      (node (ref "C8") (pin "1") (pinfunction "1_1") (pintype "passive"))
      (node (ref "C9") (pin "1") (pinfunction "1_1") (pintype "passive"))
      (node (ref "E16") (pin "10") (pinfunction "PRE_10") (pintype "input"))
      (node (ref "E16") (pin "4") (pinfunction "PRE_4") (pintype "input"))
      (node (ref "E20") (pin "10") (pinfunction "PRE_10") (pintype "input"))
      (node (ref "E29") (pin "6") (pinfunction "G1_6") (pintype "input"))
      (node (ref "E34") (pin "10") (pinfunction "1A4_10") (pintype "input"))
      (node (ref "E35") (pin "6") (pinfunction "G1_6") (pintype "input"))
      (node (ref "E36") (pin "1") (pinfunction "CLR_1") (pintype "input"))
      (node (ref "E36") (pin "11") (pinfunction "D4_11") (pintype "input"))
      (node (ref "E36") (pin "13") (pinfunction "D5_13") (pintype "input"))
      (node (ref "E36") (pin "6") (pinfunction "D3_6") (pintype "input"))
      (node (ref "E4") (pin "10") (pinfunction "B_10") (pintype "input"))
      (node (ref "E4") (pin "11") (pinfunction "CLR_11") (pintype "input"))
      (node (ref "J1") (pin "1") (pinfunction "1_1") (pintype "passive"))
      (node (ref "J1") (pin "2") (pinfunction "2_2") (pintype "passive"))
      (node (ref "J1") (pin "3") (pinfunction "3_3") (pintype "passive"))
      (node (ref "J1") (pin "4") (pinfunction "4_4") (pintype "passive"))
      (node (ref "J1") (pin "5") (pinfunction "5_5") (pintype "passive"))
      (node (ref "J1") (pin "7") (pinfunction "7_7") (pintype "passive"))
      (node (ref "J1") (pin "9") (pinfunction "9_9") (pintype "passive"))
      (node (ref "J2") (pin "1") (pinfunction "1_1") (pintype "passive"))
      (node (ref "J2") (pin "3") (pinfunction "3_3") (pintype "passive"))
      (node (ref "J2") (pin "5") (pinfunction "5_5") (pintype "passive"))
      (node (ref "J2") (pin "7") (pinfunction "7_7") (pintype "passive"))
      (node (ref "J2") (pin "9") (pinfunction "9_9") (pintype "passive"))
      (node (ref "J3") (pin "16") (pinfunction "16_16") (pintype "passive"))
      (node (ref "J4") (pin "16") (pinfunction "16_16") (pintype "passive"))
      (node (ref "R10") (pin "2") (pinfunction "2_2") (pintype "passive"))
      (node (ref "R11") (pin "2") (pinfunction "2_2") (pintype "passive"))
      (node (ref "R12") (pin "2") (pinfunction "2_2") (pintype "passive"))
      (node (ref "R13") (pin "2") (pinfunction "2_2") (pintype "passive"))
      (node (ref "R14") (pin "2") (pinfunction "2_2") (pintype "passive"))
      (node (ref "R15") (pin "2") (pinfunction "2_2") (pintype "passive"))
      (node (ref "R16") (pin "2") (pinfunction "2_2") (pintype "passive"))
      (node (ref "R25") (pin "1") (pinfunction "1_1") (pintype "passive"))
      (node (ref "R26") (pin "2") (pinfunction "2_2") (pintype "passive"))
      (node (ref "R28") (pin "2") (pinfunction "2_2") (pintype "passive"))
      (node (ref "R29") (pin "2") (pinfunction "2_2") (pintype "passive"))
      (node (ref "R31") (pin "2") (pinfunction "2_2") (pintype "passive"))
      (node (ref "R32") (pin "2") (pinfunction "2_2") (pintype "passive"))
      (node (ref "R33") (pin "2") (pinfunction "2_2") (pintype "passive"))
      (node (ref "R34") (pin "1") (pinfunction "1_1") (pintype "passive"))
      (node (ref "R35") (pin "1") (pinfunction "1_1") (pintype "passive"))
      (node (ref "R36") (pin "1") (pinfunction "1_1") (pintype "passive"))
      (node (ref "R37") (pin "2") (pinfunction "2_2") (pintype "passive"))
      (node (ref "R5") (pin "2") (pinfunction "2_2") (pintype "passive"))
      (node (ref "R6") (pin "2") (pinfunction "2_2") (pintype "passive"))
      (node (ref "R7") (pin "2") (pinfunction "2_2") (pintype "passive"))
      (node (ref "R8") (pin "2") (pinfunction "2_2") (pintype "passive"))
      (node (ref "R9") (pin "2") (pinfunction "2_2") (pintype "passive"))
      (node (ref "VCC") (pin "1") (pinfunction "P_1") (pintype "passive"))
    )
    (net (code "136") (name "unconnected-(E4B-~{Q}-Pad12)") (class "Default")
      (node (ref "E4") (pin "12") (pinfunction "~{Q}_12") (pintype "output"))
    )
    (net (code "137") (name "unconnected-(E5A-~{Q1}-Pad3)") (class "Default")
      (node (ref "E5") (pin "3") (pinfunction "~{Q1}_3") (pintype "output"))
    )
    (net (code "138") (name "unconnected-(E5A-~{Q2}-Pad6)") (class "Default")
      (node (ref "E5") (pin "6") (pinfunction "~{Q2}_6") (pintype "output"))
    )
    (net (code "139") (name "unconnected-(E5A-~{Q3}-Pad11)") (class "Default")
      (node (ref "E5") (pin "11") (pinfunction "~{Q3}_11") (pintype "output"))
    )
    (net (code "140") (name "unconnected-(E5A-~{Q4}-Pad14)") (class "Default")
      (node (ref "E5") (pin "14") (pinfunction "~{Q4}_14") (pintype "output"))
    )
    (net (code "141") (name "unconnected-(E6A-~{Q1}-Pad3)") (class "Default")
      (node (ref "E6") (pin "3") (pinfunction "~{Q1}_3") (pintype "output"))
    )
    (net (code "142") (name "unconnected-(E6A-~{Q2}-Pad6)") (class "Default")
      (node (ref "E6") (pin "6") (pinfunction "~{Q2}_6") (pintype "output"))
    )
    (net (code "143") (name "unconnected-(E6A-~{Q3}-Pad11)") (class "Default")
      (node (ref "E6") (pin "11") (pinfunction "~{Q3}_11") (pintype "output"))
    )
    (net (code "144") (name "unconnected-(E6A-~{Q4}-Pad14)") (class "Default")
      (node (ref "E6") (pin "14") (pinfunction "~{Q4}_14") (pintype "output"))
    )
    (net (code "145") (name "unconnected-(E7A-~{Q1}-Pad3)") (class "Default")
      (node (ref "E7") (pin "3") (pinfunction "~{Q1}_3") (pintype "output"))
    )
    (net (code "146") (name "unconnected-(E7A-~{Q2}-Pad6)") (class "Default")
      (node (ref "E7") (pin "6") (pinfunction "~{Q2}_6") (pintype "output"))
    )
    (net (code "147") (name "unconnected-(E7A-~{Q3}-Pad11)") (class "Default")
      (node (ref "E7") (pin "11") (pinfunction "~{Q3}_11") (pintype "output"))
    )
    (net (code "148") (name "unconnected-(E7A-~{Q4}-Pad14)") (class "Default")
      (node (ref "E7") (pin "14") (pinfunction "~{Q4}_14") (pintype "output"))
    )
    (net (code "149") (name "unconnected-(E16A-Q-Pad5)") (class "Default")
      (node (ref "E16") (pin "5") (pinfunction "Q_5") (pintype "output"))
    )
    (net (code "150") (name "unconnected-(E20A-~{Q}-Pad6)") (class "Default")
      (node (ref "E20") (pin "6") (pinfunction "~{Q}_6") (pintype "output"))
    )
    (net (code "151") (name "unconnected-(E26A-~{Q1}-Pad1)") (class "Default")
      (node (ref "E26") (pin "1") (pinfunction "~{Q1}_1") (pintype "output"))
    )
    (net (code "152") (name "unconnected-(E26A-~{Q2}-Pad14)") (class "Default")
      (node (ref "E26") (pin "14") (pinfunction "~{Q2}_14") (pintype "output"))
    )
    (net (code "153") (name "unconnected-(E26A-~{Q3}-Pad11)") (class "Default")
      (node (ref "E26") (pin "11") (pinfunction "~{Q3}_11") (pintype "output"))
    )
    (net (code "154") (name "unconnected-(E34A-1Y4-Pad9)") (class "Default")
      (node (ref "E34") (pin "9") (pinfunction "1Y4_9") (pintype "tri_state"))
    )
    (net (code "155") (name "unconnected-(E35A-Y0-Pad15)") (class "Default")
      (node (ref "E35") (pin "15") (pinfunction "Y0_15") (pintype "output"))
    )
    (net (code "156") (name "unconnected-(E35A-Y1-Pad14)") (class "Default")
      (node (ref "E35") (pin "14") (pinfunction "Y1_14") (pintype "output"))
    )
    (net (code "157") (name "unconnected-(E35A-Y2-Pad13)") (class "Default")
      (node (ref "E35") (pin "13") (pinfunction "Y2_13") (pintype "output"))
    )
    (net (code "158") (name "unconnected-(E35A-Y3-Pad12)") (class "Default")
      (node (ref "E35") (pin "12") (pinfunction "Y3_12") (pintype "output"))
    )
    (net (code "159") (name "unconnected-(E35A-Y7-Pad7)") (class "Default")
      (node (ref "E35") (pin "7") (pinfunction "Y7_7") (pintype "output"))
    )
    (net (code "160") (name "unconnected-(E36A-Q3-Pad7)") (class "Default")
      (node (ref "E36") (pin "7") (pinfunction "Q3_7") (pintype "output"))
    )
    (net (code "161") (name "unconnected-(E36A-Q4-Pad10)") (class "Default")
      (node (ref "E36") (pin "10") (pinfunction "Q4_10") (pintype "output"))
    )
    (net (code "162") (name "unconnected-(E36A-Q5-Pad12)") (class "Default")
      (node (ref "E36") (pin "12") (pinfunction "Q5_12") (pintype "output"))
    )
    (net (code "163") (name "~{ADRLTH}") (class "Default")
      (node (ref "E12") (pin "9") (pinfunction "CLK_9") (pintype "input"))
      (node (ref "E14") (pin "9") (pinfunction "CLK_9") (pintype "input"))
      (node (ref "E8") (pin "11") (pinfunction "O_11") (pintype "output"))
    )
    (net (code "164") (name "~{BFSW}") (class "Default")
      (node (ref "E28") (pin "9") (pinfunction "1Y4_9") (pintype "tri_state"))
      (node (ref "J2") (pin "24") (pinfunction "24_24") (pintype "passive"))
    )
    (net (code "165") (name "~{BKDTACNTL}") (class "Default")
      (node (ref "E28") (pin "3") (pinfunction "1Y1_3") (pintype "tri_state"))
      (node (ref "J2") (pin "12") (pinfunction "12_12") (pintype "passive"))
    )
    (net (code "166") (name "~{BOOTF}") (class "Default")
      (node (ref "E16") (pin "2") (pinfunction "D_2") (pintype "input"))
      (node (ref "E16") (pin "6") (pinfunction "~{Q}_6") (pintype "output"))
      (node (ref "E28") (pin "10") (pinfunction "1A4_10") (pintype "input"))
    )
    (net (code "167") (name "~{BUSEN}") (class "Default")
      (node (ref "E34") (pin "13") (pinfunction "2Y2_13") (pintype "tri_state"))
      (node (ref "J1") (pin "24") (pinfunction "24_24") (pintype "passive"))
    )
    (net (code "168") (name "~{DEP}") (class "Default")
      (node (ref "E28") (pin "5") (pinfunction "1Y2_5") (pintype "tri_state"))
      (node (ref "J2") (pin "20") (pinfunction "20_20") (pintype "passive"))
    )
    (net (code "169") (name "~{DSPLTH}") (class "Default")
      (node (ref "E13") (pin "9") (pinfunction "CLK_9") (pintype "input"))
      (node (ref "E15") (pin "9") (pinfunction "CLK_9") (pintype "input"))
      (node (ref "E8") (pin "8") (pinfunction "O_8") (pintype "output"))
    )
    (net (code "170") (name "~{EMA0}") (class "Default")
      (node (ref "E27") (pin "11") (pinfunction "I_11") (pintype "input"))
      (node (ref "J1") (pin "30") (pinfunction "30_30") (pintype "passive"))
      (node (ref "R34") (pin "2") (pinfunction "2_2") (pintype "passive"))
    )
    (net (code "171") (name "~{EMA1}") (class "Default")
      (node (ref "E27") (pin "9") (pinfunction "I_9") (pintype "input"))
      (node (ref "J1") (pin "28") (pinfunction "28_28") (pintype "passive"))
      (node (ref "R35") (pin "2") (pinfunction "2_2") (pintype "passive"))
    )
    (net (code "172") (name "~{EMA2}") (class "Default")
      (node (ref "E27") (pin "13") (pinfunction "I_13") (pintype "input"))
      (node (ref "J1") (pin "32") (pinfunction "32_32") (pintype "passive"))
      (node (ref "R36") (pin "2") (pinfunction "2_2") (pintype "passive"))
    )
    (net (code "173") (name "~{EMODE}") (class "Default")
      (node (ref "E1") (pin "6") (pinfunction "MOD_6") (pintype "input"))
      (node (ref "E16") (pin "8") (pinfunction "~{Q}_8") (pintype "output"))
      (node (ref "E2") (pin "6") (pinfunction "MOD_6") (pintype "input"))
      (node (ref "E22") (pin "6") (pinfunction "I1_6") (pintype "input"))
      (node (ref "E3") (pin "6") (pinfunction "MOD_6") (pintype "input"))
    )
    (net (code "174") (name "~{EXTPUL}") (class "Default")
      (node (ref "J4") (pin "9") (pinfunction "9_9") (pintype "passive"))
    )
    (net (code "175") (name "~{FUN}") (class "Default")
      (node (ref "E24") (pin "3") (pinfunction "I_3") (pintype "input"))
      (node (ref "E25") (pin "11") (pinfunction "I2_11") (pintype "input"))
      (node (ref "E25") (pin "2") (pinfunction "I1_2") (pintype "input"))
      (node (ref "J4") (pin "15") (pinfunction "15_15") (pintype "passive"))
    )
    (net (code "176") (name "~{GATEENT}") (class "Default")
      (node (ref "E10") (pin "1") (pinfunction "G_1") (pintype "input"))
      (node (ref "E11") (pin "1") (pinfunction "G_1") (pintype "input"))
      (node (ref "E21") (pin "6") (pinfunction "O_6") (pintype "output"))
      (node (ref "E30") (pin "5") (pinfunction "I1_5") (pintype "input"))
      (node (ref "E9") (pin "1") (pinfunction "G_1") (pintype "input"))
    )
    (net (code "177") (name "~{GATESR}") (class "Default")
      (node (ref "E10") (pin "19") (pinfunction "G_19") (pintype "input"))
      (node (ref "E11") (pin "19") (pinfunction "G_19") (pintype "input"))
      (node (ref "E32") (pin "11") (pinfunction "O_11") (pintype "output"))
      (node (ref "E9") (pin "19") (pinfunction "G_19") (pintype "input"))
    )
    (net (code "178") (name "~{IND1}") (class "Default")
      (node (ref "E28") (pin "7") (pinfunction "1Y3_7") (pintype "tri_state"))
      (node (ref "E34") (pin "3") (pinfunction "1Y1_3") (pintype "tri_state"))
      (node (ref "J2") (pin "8") (pinfunction "8_8") (pintype "passive"))
    )
    (net (code "179") (name "~{IND2}") (class "Default")
      (node (ref "E34") (pin "5") (pinfunction "1Y2_5") (pintype "tri_state"))
      (node (ref "J2") (pin "4") (pinfunction "4_4") (pintype "passive"))
    )
    (net (code "180") (name "~{INIT}") (class "Default")
      (node (ref "E31") (pin "9") (pinfunction "1Y4_9") (pintype "tri_state"))
      (node (ref "J2") (pin "34") (pinfunction "34_34") (pintype "passive"))
    )
    (net (code "181") (name "~{KEY-F}") (class "Default")
      (node (ref "E26") (pin "13") (pinfunction "C12_13") (pintype "input"))
      (node (ref "E26") (pin "4") (pinfunction "C34_4") (pintype "input"))
      (node (ref "E27") (pin "5") (pinfunction "I_5") (pintype "input"))
      (node (ref "J4") (pin "3") (pinfunction "3_3") (pintype "passive"))
    )
    (net (code "182") (name "~{KEYCNTL}") (class "Default")
      (node (ref "E31") (pin "13") (pinfunction "2Y2_13") (pintype "tri_state"))
      (node (ref "J2") (pin "10") (pinfunction "10_10") (pintype "passive"))
    )
    (net (code "183") (name "~{KEYSTB}") (class "Default")
      (node (ref "E16") (pin "11") (pinfunction "CLK_11") (pintype "input"))
      (node (ref "E21") (pin "2") (pinfunction "I1_2") (pintype "input"))
      (node (ref "E24") (pin "2") (pinfunction "O_2") (pintype "output"))
      (node (ref "E31") (pin "1") (pinfunction "1G_1") (pintype "input"))
      (node (ref "E33") (pin "11") (pinfunction "I0_11") (pintype "input"))
      (node (ref "E33") (pin "9") (pinfunction "I1_9") (pintype "input"))
    )
    (net (code "184") (name "~{KFUN0}") (class "Default")
      (node (ref "E26") (pin "2") (pinfunction "D1_2") (pintype "input"))
      (node (ref "E3") (pin "1") (pinfunction "SER_1") (pintype "input"))
      (node (ref "E3") (pin "2") (pinfunction "A_2") (pintype "input"))
      (node (ref "J3") (pin "3") (pinfunction "3_3") (pintype "passive"))
    )
    (net (code "185") (name "~{KFUN1}") (class "Default")
      (node (ref "E2") (pin "1") (pinfunction "SER_1") (pintype "input"))
      (node (ref "E2") (pin "2") (pinfunction "A_2") (pintype "input"))
      (node (ref "E26") (pin "3") (pinfunction "D2_3") (pintype "input"))
      (node (ref "J3") (pin "2") (pinfunction "2_2") (pintype "passive"))
    )
    (net (code "186") (name "~{KFUN2}") (class "Default")
      (node (ref "E1") (pin "1") (pinfunction "SER_1") (pintype "input"))
      (node (ref "E1") (pin "2") (pinfunction "A_2") (pintype "input"))
      (node (ref "E26") (pin "6") (pinfunction "D3_6") (pintype "input"))
      (node (ref "J3") (pin "1") (pinfunction "1_1") (pintype "passive"))
    )
    (net (code "187") (name "~{LAENAB}") (class "Default")
      (node (ref "E23") (pin "2") (pinfunction "O_2") (pintype "open_collector"))
      (node (ref "J2") (pin "22") (pinfunction "22_22") (pintype "passive"))
    )
    (net (code "188") (name "~{MAEN}") (class "Default")
      (node (ref "E23") (pin "8") (pinfunction "O_8") (pintype "open_collector"))
      (node (ref "J2") (pin "32") (pinfunction "32_32") (pintype "passive"))
    )
    (net (code "189") (name "~{MALC}") (class "Default")
      (node (ref "E28") (pin "11") (pinfunction "2Y1_11") (pintype "tri_state"))
      (node (ref "J2") (pin "36") (pinfunction "36_36") (pintype "passive"))
    )
    (net (code "190") (name "~{MCLOCK}") (class "Default")
      (node (ref "E33") (pin "2") (pinfunction "I0_2") (pintype "input"))
      (node (ref "J4") (pin "1") (pinfunction "1_1") (pintype "passive"))
    )
    (net (code "191") (name "~{MD}") (class "Default")
      (node (ref "E34") (pin "7") (pinfunction "1Y3_7") (pintype "tri_state"))
      (node (ref "J2") (pin "18") (pinfunction "18_18") (pintype "passive"))
    )
    (net (code "192") (name "~{MEMSTART}") (class "Default")
      (node (ref "E23") (pin "12") (pinfunction "O_12") (pintype "open_collector"))
      (node (ref "J2") (pin "26") (pinfunction "26_26") (pintype "passive"))
    )
    (net (code "193") (name "~{MH0}") (class "Default")
      (node (ref "E20") (pin "12") (pinfunction "D_12") (pintype "input"))
      (node (ref "E20") (pin "8") (pinfunction "~{Q}_8") (pintype "output"))
      (node (ref "E21") (pin "9") (pinfunction "I0_9") (pintype "input"))
      (node (ref "E8") (pin "2") (pinfunction "I1_2") (pintype "input"))
      (node (ref "E8") (pin "9") (pinfunction "I0_9") (pintype "input"))
    )
    (net (code "194") (name "~{MSIRDIS}") (class "Default")
      (node (ref "E31") (pin "11") (pinfunction "2Y1_11") (pintype "tri_state"))
      (node (ref "J2") (pin "2") (pinfunction "2_2") (pintype "passive"))
    )
    (net (code "195") (name "~{PANLOCK}") (class "Default")
      (node (ref "E24") (pin "13") (pinfunction "I_13") (pintype "input"))
      (node (ref "J2") (pin "6") (pinfunction "6_6") (pintype "passive"))
      (node (ref "R31") (pin "1") (pinfunction "1_1") (pintype "passive"))
    )
    (net (code "196") (name "~{PULSELOADADD}") (class "Default")
      (node (ref "E31") (pin "7") (pinfunction "1Y3_7") (pintype "tri_state"))
      (node (ref "J2") (pin "40") (pinfunction "40_40") (pintype "passive"))
    )
    (net (code "197") (name "~{RUN}") (class "Default")
      (node (ref "E24") (pin "5") (pinfunction "I_5") (pintype "input"))
      (node (ref "J1") (pin "18") (pinfunction "18_18") (pintype "passive"))
      (node (ref "R28") (pin "1") (pinfunction "1_1") (pintype "passive"))
    )
    (net (code "198") (name "~{SHLT}") (class "Default")
      (node (ref "E27") (pin "1") (pinfunction "I_1") (pintype "input"))
      (node (ref "J3") (pin "5") (pinfunction "5_5") (pintype "passive"))
    )
    (net (code "199") (name "~{SINGSTEP}") (class "Default")
      (node (ref "E28") (pin "13") (pinfunction "2Y2_13") (pintype "tri_state"))
      (node (ref "J2") (pin "14") (pinfunction "14_14") (pintype "passive"))
    )
    (net (code "200") (name "~{SRDATA}") (class "Default")
      (node (ref "E32") (pin "13") (pinfunction "I1_13") (pintype "input"))
      (node (ref "E8") (pin "1") (pinfunction "I0_1") (pintype "input"))
      (node (ref "J2") (pin "30") (pinfunction "30_30") (pintype "passive"))
      (node (ref "R29") (pin "1") (pinfunction "1_1") (pintype "passive"))
      (node (ref "R30") (pin "2") (pinfunction "2_2") (pintype "passive"))
    )
    (net (code "201") (name "~{STATE}") (class "Default")
      (node (ref "E34") (pin "11") (pinfunction "2Y1_11") (pintype "tri_state"))
      (node (ref "J2") (pin "38") (pinfunction "38_38") (pintype "passive"))
    )
    (net (code "202") (name "~{STHIS}") (class "Default")
      (node (ref "E20") (pin "2") (pinfunction "D_2") (pintype "input"))
      (node (ref "J3") (pin "4") (pinfunction "4_4") (pintype "passive"))
    )
    (net (code "203") (name "~{TS1}") (class "Default")
      (node (ref "E20") (pin "3") (pinfunction "CLK_3") (pintype "input"))
      (node (ref "E21") (pin "10") (pinfunction "I1_10") (pintype "input"))
      (node (ref "E24") (pin "9") (pinfunction "I_9") (pintype "input"))
      (node (ref "J1") (pin "26") (pinfunction "26_26") (pintype "passive"))
      (node (ref "R26") (pin "1") (pinfunction "1_1") (pintype "passive"))
      (node (ref "R27") (pin "2") (pinfunction "2_2") (pintype "passive"))
    )
  )
)
